# NHK2016mother.net
KiCad netlist of a schematic drawn in EAGLE
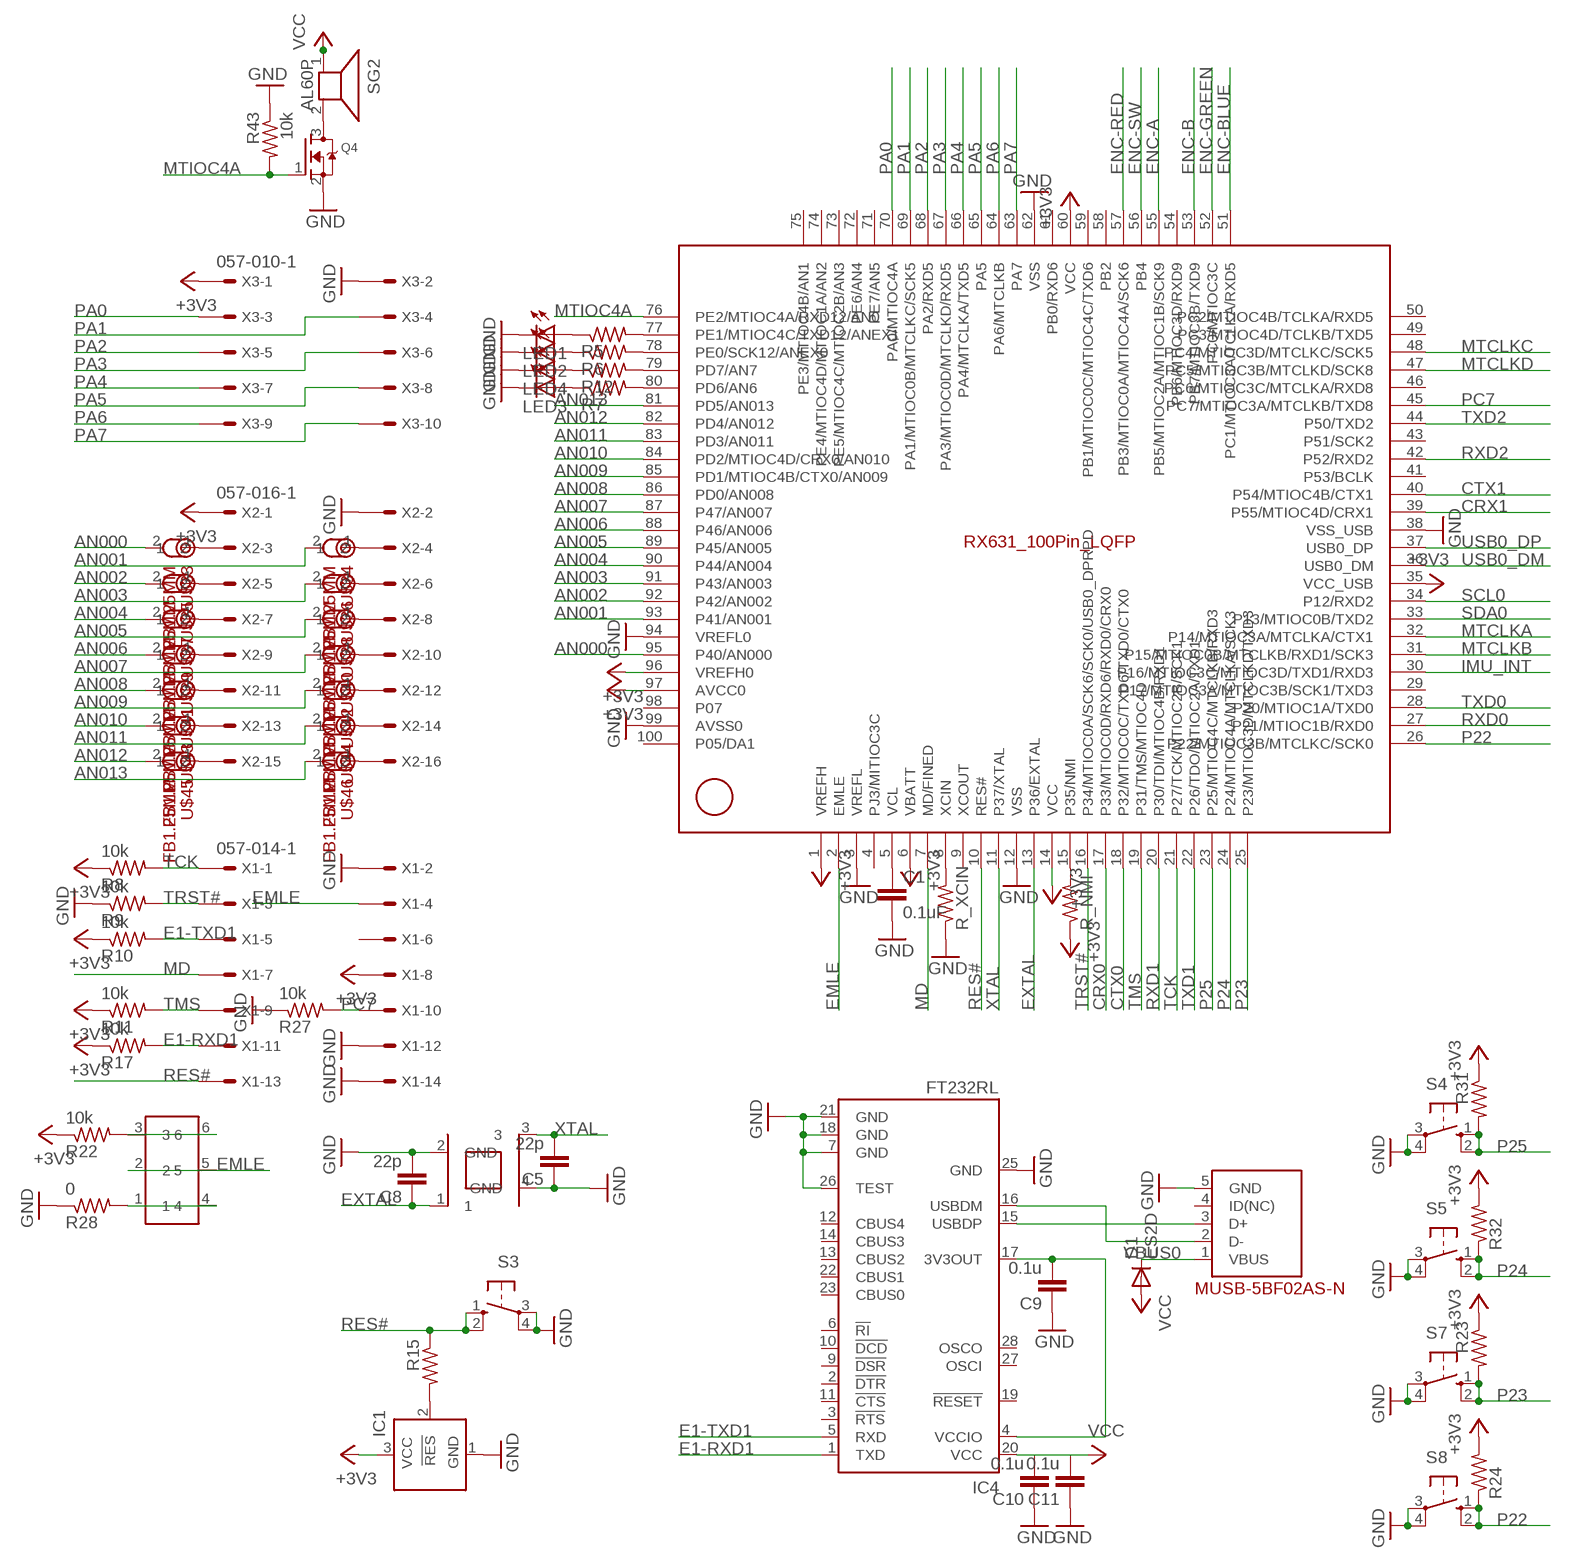
[diagram p0: schematic, sheet 1, part 1 of 2]
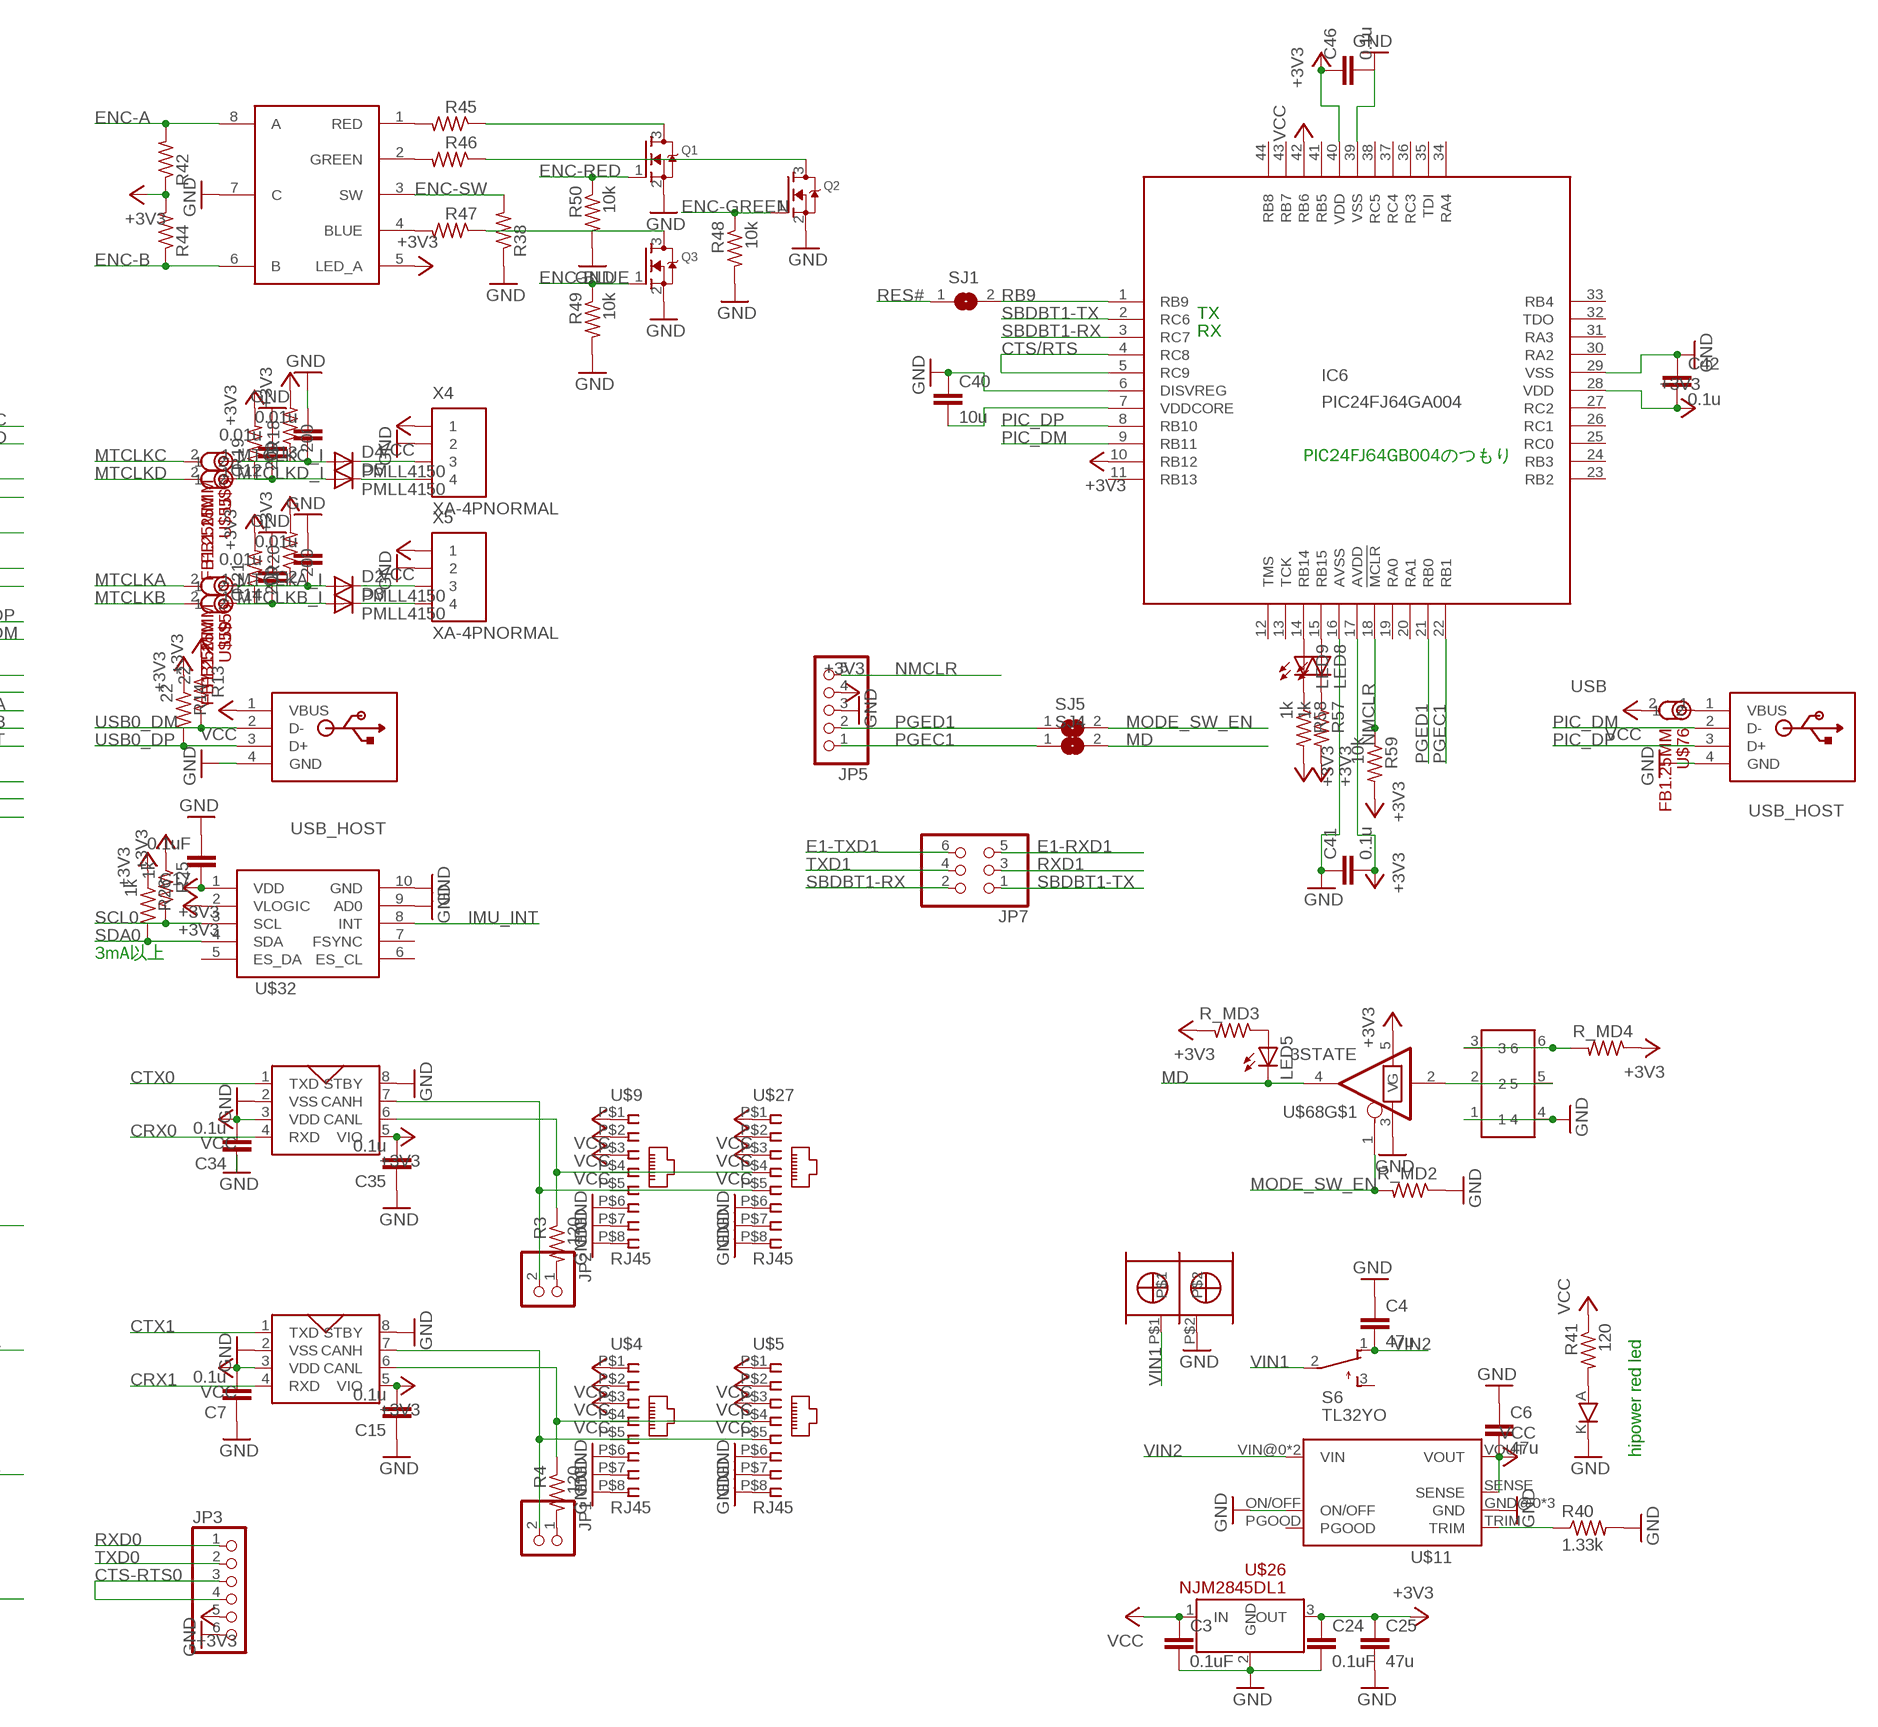
[diagram p1: schematic, sheet 1, part 2 of 2]

(export (version "E")
  (design (tool "Eeschema 10.0.6"))
  (components
    (comp (ref "C1")
      (value "0.1uF")
      (footprint "eagle-import:C0603K")
      (libsource (lib "eagle-import") (part "C-EUC0603K"))
    )
    (comp (ref "C2")
      (value "0.01u")
      (footprint "eagle-import:C0402")
      (libsource (lib "eagle-import") (part "C-EUC0402"))
    )
    (comp (ref "C3")
      (value "0.1uF")
      (footprint "eagle-import:C0603K")
      (libsource (lib "eagle-import") (part "C-EUC0603K"))
    )
    (comp (ref "C4")
      (value "47u")
      (footprint "eagle-import:C3225")
      (libsource (lib "eagle-import") (part "C-EUC3225"))
    )
    (comp (ref "C5")
      (value "22p")
      (footprint "eagle-import:C0603K")
      (libsource (lib "eagle-import") (part "C-EUC0603K"))
    )
    (comp (ref "C6")
      (value "47u")
      (footprint "eagle-import:C3225")
      (libsource (lib "eagle-import") (part "C-EUC3225"))
    )
    (comp (ref "C7")
      (value "0.1u")
      (footprint "eagle-import:C0402")
      (libsource (lib "eagle-import") (part "C-EUC0402"))
    )
    (comp (ref "C8")
      (value "22p")
      (footprint "eagle-import:C0603K")
      (libsource (lib "eagle-import") (part "C-EUC0603K"))
    )
    (comp (ref "C9")
      (value "0.1u")
      (footprint "eagle-import:C0402")
      (libsource (lib "eagle-import") (part "C-EUC0402"))
    )
    (comp (ref "C10")
      (value "0.1u")
      (footprint "eagle-import:C0402")
      (libsource (lib "eagle-import") (part "C-EUC0402"))
    )
    (comp (ref "C11")
      (value "0.1u")
      (footprint "eagle-import:C0402")
      (libsource (lib "eagle-import") (part "C-EUC0402"))
    )
    (comp (ref "C12")
      (value "0.01u")
      (footprint "eagle-import:C0402")
      (libsource (lib "eagle-import") (part "C-EUC0402"))
    )
    (comp (ref "C13")
      (value "0.01u")
      (footprint "eagle-import:C0402")
      (libsource (lib "eagle-import") (part "C-EUC0402"))
    )
    (comp (ref "C14")
      (value "0.01u")
      (footprint "eagle-import:C0402")
      (libsource (lib "eagle-import") (part "C-EUC0402"))
    )
    (comp (ref "C15")
      (value "0.1u")
      (footprint "eagle-import:C0402")
      (libsource (lib "eagle-import") (part "C-EUC0402"))
    )
    (comp (ref "C17")
      (value "0.1uF")
      (footprint "eagle-import:C0603K")
      (libsource (lib "eagle-import") (part "C-EUC0603K"))
    )
    (comp (ref "C24")
      (value "0.1uF")
      (footprint "eagle-import:C0603K")
      (libsource (lib "eagle-import") (part "C-EUC0603K"))
    )
    (comp (ref "C25")
      (value "47u")
      (footprint "eagle-import:C3225")
      (libsource (lib "eagle-import") (part "C-EUC3225"))
    )
    (comp (ref "C34")
      (value "0.1u")
      (footprint "eagle-import:C0402")
      (libsource (lib "eagle-import") (part "C-EUC0402"))
    )
    (comp (ref "C35")
      (value "0.1u")
      (footprint "eagle-import:C0402")
      (libsource (lib "eagle-import") (part "C-EUC0402"))
    )
    (comp (ref "C40")
      (value "10u")
      (footprint "eagle-import:C0603K")
      (libsource (lib "eagle-import") (part "C-EUC0603K"))
    )
    (comp (ref "C41")
      (value "0.1u")
      (footprint "eagle-import:C0603K")
      (libsource (lib "eagle-import") (part "C-EUC0603K"))
    )
    (comp (ref "C42")
      (value "0.1u")
      (footprint "eagle-import:C0603K")
      (libsource (lib "eagle-import") (part "C-EUC0603K"))
    )
    (comp (ref "C46")
      (value "0.1u")
      (footprint "eagle-import:C0603K")
      (libsource (lib "eagle-import") (part "C-EUC0603K"))
    )
    (comp (ref "D1")
      (value "ES2D")
      (footprint "eagle-import:SMB")
      (libsource (lib "eagle-import") (part "ES2D"))
    )
    (comp (ref "D2")
      (value "PMLL4150")
      (footprint "eagle-import:SOD80C")
      (libsource (lib "eagle-import") (part "PMLL4150"))
    )
    (comp (ref "D3")
      (value "PMLL4150")
      (footprint "eagle-import:SOD80C")
      (libsource (lib "eagle-import") (part "PMLL4150"))
    )
    (comp (ref "D4")
      (value "PMLL4150")
      (footprint "eagle-import:SOD80C")
      (libsource (lib "eagle-import") (part "PMLL4150"))
    )
    (comp (ref "D5")
      (value "PMLL4150")
      (footprint "eagle-import:SOD80C")
      (libsource (lib "eagle-import") (part "PMLL4150"))
    )
    (comp (ref "IC1")
      (value "TCM809")
      (footprint "eagle-import:SOT23B-3")
      (fields (field (name "MF") "MICROCHIP") (field (name "MPN") "TCM809MENB713"))
      (libsource (lib "eagle-import") (part "TCM809"))
    )
    (comp (ref "IC4")
      (value "FT232RL")
      (footprint "eagle-import:SSOP28")
      (libsource (lib "eagle-import") (part "FT232RL"))
    )
    (comp (ref "IC6")
      (value "PIC24FJ64GA004")
      (footprint "eagle-import:TQFP44")
      (fields (field (name "MPN") "PIC24FJ64GA004-E/PT"))
      (libsource (lib "eagle-import") (part "PIC24FJ64GA004"))
    )
    (comp (ref "JP1")
      (value "PINHD-1X2")
      (footprint "eagle-import:1X02")
      (libsource (lib "eagle-import") (part "PINHD-1X2"))
    )
    (comp (ref "JP2")
      (value "PINHD-1X2")
      (footprint "eagle-import:1X02")
      (libsource (lib "eagle-import") (part "PINHD-1X2"))
    )
    (comp (ref "JP3")
      (value "PINHD-1X6")
      (footprint "eagle-import:1X06")
      (libsource (lib "eagle-import") (part "PINHD-1X6"))
    )
    (comp (ref "JP5")
      (value "PINHD-1X5")
      (footprint "eagle-import:1X05")
      (libsource (lib "eagle-import") (part "PINHD-1X5"))
    )
    (comp (ref "JP7")
      (value "PINHD-2X3")
      (footprint "eagle-import:2X03")
      (libsource (lib "eagle-import") (part "PINHD-2X3"))
    )
    (comp (ref "LED1")
      (value "LEDSML0805")
      (footprint "eagle-import:SML0805")
      (libsource (lib "eagle-import") (part "LEDSML0805"))
    )
    (comp (ref "LED2")
      (value "LEDSML0805")
      (footprint "eagle-import:SML0805")
      (libsource (lib "eagle-import") (part "LEDSML0805"))
    )
    (comp (ref "LED3")
      (value "LEDSML0805")
      (footprint "eagle-import:SML0805")
      (libsource (lib "eagle-import") (part "LEDSML0805"))
    )
    (comp (ref "LED4")
      (value "LEDSML0805")
      (footprint "eagle-import:SML0805")
      (libsource (lib "eagle-import") (part "LEDSML0805"))
    )
    (comp (ref "LED5")
      (value "LEDSML0805")
      (footprint "eagle-import:SML0805")
      (libsource (lib "eagle-import") (part "LEDSML0805"))
    )
    (comp (ref "LED8")
      (value "LEDSML0805")
      (footprint "eagle-import:SML0805")
      (libsource (lib "eagle-import") (part "LEDSML0805"))
    )
    (comp (ref "LED9")
      (value "LEDSML0805")
      (footprint "eagle-import:SML0805")
      (libsource (lib "eagle-import") (part "LEDSML0805"))
    )
    (comp (ref "Q1")
      (value "MOSFET-NREFLOW")
      (footprint "eagle-import:SOT23")
      (libsource (lib "eagle-import") (part "MOSFET-NREFLOW"))
    )
    (comp (ref "Q2")
      (value "MOSFET-NREFLOW")
      (footprint "eagle-import:SOT23")
      (libsource (lib "eagle-import") (part "MOSFET-NREFLOW"))
    )
    (comp (ref "Q3")
      (value "MOSFET-NREFLOW")
      (footprint "eagle-import:SOT23")
      (libsource (lib "eagle-import") (part "MOSFET-NREFLOW"))
    )
    (comp (ref "Q4")
      (value "MOSFET-NREFLOW")
      (footprint "eagle-import:SOT23")
      (libsource (lib "eagle-import") (part "MOSFET-NREFLOW"))
    )
    (comp (ref "R3")
      (value "120")
      (footprint "eagle-import:MINI_MELF-0102W")
      (libsource (lib "eagle-import") (part "R-US_MELF0102W"))
    )
    (comp (ref "R4")
      (value "120")
      (footprint "eagle-import:MINI_MELF-0102W")
      (libsource (lib "eagle-import") (part "R-US_MELF0102W"))
    )
    (comp (ref "R5")
      (value "R-US_MELF0102W")
      (footprint "eagle-import:MINI_MELF-0102W")
      (libsource (lib "eagle-import") (part "R-US_MELF0102W"))
    )
    (comp (ref "R6")
      (value "R-US_MELF0102W")
      (footprint "eagle-import:MINI_MELF-0102W")
      (libsource (lib "eagle-import") (part "R-US_MELF0102W"))
    )
    (comp (ref "R7")
      (value "R-US_MELF0102W")
      (footprint "eagle-import:MINI_MELF-0102W")
      (libsource (lib "eagle-import") (part "R-US_MELF0102W"))
    )
    (comp (ref "R8")
      (value "10k")
      (footprint "eagle-import:MINI_MELF-0102W")
      (libsource (lib "eagle-import") (part "R-US_MELF0102W"))
    )
    (comp (ref "R9")
      (value "10k")
      (footprint "eagle-import:MINI_MELF-0102W")
      (libsource (lib "eagle-import") (part "R-US_MELF0102W"))
    )
    (comp (ref "R10")
      (value "10k")
      (footprint "eagle-import:MINI_MELF-0102W")
      (libsource (lib "eagle-import") (part "R-US_MELF0102W"))
    )
    (comp (ref "R11")
      (value "10k")
      (footprint "eagle-import:MINI_MELF-0102W")
      (libsource (lib "eagle-import") (part "R-US_MELF0102W"))
    )
    (comp (ref "R12")
      (value "R-US_MELF0102W")
      (footprint "eagle-import:MINI_MELF-0102W")
      (libsource (lib "eagle-import") (part "R-US_MELF0102W"))
    )
    (comp (ref "R13")
      (value "22")
      (footprint "eagle-import:MINI_MELF-0102W")
      (libsource (lib "eagle-import") (part "R-US_MELF0102W"))
    )
    (comp (ref "R14")
      (value "22")
      (footprint "eagle-import:MINI_MELF-0102W")
      (libsource (lib "eagle-import") (part "R-US_MELF0102W"))
    )
    (comp (ref "R15")
      (value "R-US_MELF0102W")
      (footprint "eagle-import:MINI_MELF-0102W")
      (libsource (lib "eagle-import") (part "R-US_MELF0102W"))
    )
    (comp (ref "R17")
      (value "10k")
      (footprint "eagle-import:MINI_MELF-0102W")
      (libsource (lib "eagle-import") (part "R-US_MELF0102W"))
    )
    (comp (ref "R18")
      (value "200")
      (footprint "eagle-import:MINI_MELF-0102W")
      (libsource (lib "eagle-import") (part "R-US_MELF0102W"))
    )
    (comp (ref "R19")
      (value "200")
      (footprint "eagle-import:MINI_MELF-0102W")
      (libsource (lib "eagle-import") (part "R-US_MELF0102W"))
    )
    (comp (ref "R20")
      (value "200")
      (footprint "eagle-import:MINI_MELF-0102W")
      (libsource (lib "eagle-import") (part "R-US_MELF0102W"))
    )
    (comp (ref "R21")
      (value "200")
      (footprint "eagle-import:MINI_MELF-0102W")
      (libsource (lib "eagle-import") (part "R-US_MELF0102W"))
    )
    (comp (ref "R22")
      (value "10k")
      (footprint "eagle-import:MINI_MELF-0102W")
      (libsource (lib "eagle-import") (part "R-US_MELF0102W"))
    )
    (comp (ref "R23")
      (value "R-US_MELF0102W")
      (footprint "eagle-import:MINI_MELF-0102W")
      (libsource (lib "eagle-import") (part "R-US_MELF0102W"))
    )
    (comp (ref "R24")
      (value "R-US_MELF0102W")
      (footprint "eagle-import:MINI_MELF-0102W")
      (libsource (lib "eagle-import") (part "R-US_MELF0102W"))
    )
    (comp (ref "R25")
      (value "1k")
      (footprint "eagle-import:MINI_MELF-0102W")
      (libsource (lib "eagle-import") (part "R-US_MELF0102W"))
    )
    (comp (ref "R26")
      (value "1k")
      (footprint "eagle-import:MINI_MELF-0102W")
      (libsource (lib "eagle-import") (part "R-US_MELF0102W"))
    )
    (comp (ref "R27")
      (value "10k")
      (footprint "eagle-import:MINI_MELF-0102W")
      (libsource (lib "eagle-import") (part "R-US_MELF0102W"))
    )
    (comp (ref "R28")
      (value "0")
      (footprint "eagle-import:MINI_MELF-0102W")
      (libsource (lib "eagle-import") (part "R-US_MELF0102W"))
    )
    (comp (ref "R31")
      (value "R-US_MELF0102W")
      (footprint "eagle-import:MINI_MELF-0102W")
      (libsource (lib "eagle-import") (part "R-US_MELF0102W"))
    )
    (comp (ref "R32")
      (value "R-US_MELF0102W")
      (footprint "eagle-import:MINI_MELF-0102W")
      (libsource (lib "eagle-import") (part "R-US_MELF0102W"))
    )
    (comp (ref "R38")
      (value "R-US_MELF0102W")
      (footprint "eagle-import:MINI_MELF-0102W")
      (libsource (lib "eagle-import") (part "R-US_MELF0102W"))
    )
    (comp (ref "R40")
      (value "1.33k")
      (footprint "eagle-import:MINI_MELF-0102W")
      (libsource (lib "eagle-import") (part "R-US_MELF0102W"))
    )
    (comp (ref "R41")
      (value "120")
      (footprint "eagle-import:MINI_MELF-0102W")
      (libsource (lib "eagle-import") (part "R-US_MELF0102W"))
    )
    (comp (ref "R42")
      (value "R-US_MELF0102W")
      (footprint "eagle-import:MINI_MELF-0102W")
      (libsource (lib "eagle-import") (part "R-US_MELF0102W"))
    )
    (comp (ref "R43")
      (value "10k")
      (footprint "eagle-import:MINI_MELF-0102W")
      (libsource (lib "eagle-import") (part "R-US_MELF0102W"))
    )
    (comp (ref "R44")
      (value "R-US_MELF0102W")
      (footprint "eagle-import:MINI_MELF-0102W")
      (libsource (lib "eagle-import") (part "R-US_MELF0102W"))
    )
    (comp (ref "R45")
      (value "R-US_MELF0102W")
      (footprint "eagle-import:MINI_MELF-0102W")
      (libsource (lib "eagle-import") (part "R-US_MELF0102W"))
    )
    (comp (ref "R46")
      (value "R-US_MELF0102W")
      (footprint "eagle-import:MINI_MELF-0102W")
      (libsource (lib "eagle-import") (part "R-US_MELF0102W"))
    )
    (comp (ref "R47")
      (value "R-US_MELF0102W")
      (footprint "eagle-import:MINI_MELF-0102W")
      (libsource (lib "eagle-import") (part "R-US_MELF0102W"))
    )
    (comp (ref "R48")
      (value "10k")
      (footprint "eagle-import:MINI_MELF-0102W")
      (libsource (lib "eagle-import") (part "R-US_MELF0102W"))
    )
    (comp (ref "R49")
      (value "10k")
      (footprint "eagle-import:MINI_MELF-0102W")
      (libsource (lib "eagle-import") (part "R-US_MELF0102W"))
    )
    (comp (ref "R50")
      (value "10k")
      (footprint "eagle-import:MINI_MELF-0102W")
      (libsource (lib "eagle-import") (part "R-US_MELF0102W"))
    )
    (comp (ref "R57")
      (value "1k")
      (footprint "eagle-import:MINI_MELF-0102W")
      (libsource (lib "eagle-import") (part "R-US_MELF0102W"))
    )
    (comp (ref "R58")
      (value "1k")
      (footprint "eagle-import:MINI_MELF-0102W")
      (libsource (lib "eagle-import") (part "R-US_MELF0102W"))
    )
    (comp (ref "R59")
      (value "10k")
      (footprint "eagle-import:MINI_MELF-0102W")
      (libsource (lib "eagle-import") (part "R-US_MELF0102W"))
    )
    (comp (ref "R_MD2")
      (value "R-US_MELF0102W")
      (footprint "eagle-import:MINI_MELF-0102W")
      (libsource (lib "eagle-import") (part "R-US_MELF0102W"))
    )
    (comp (ref "R_MD3")
      (value "R-US_MELF0102W")
      (footprint "eagle-import:MINI_MELF-0102W")
      (libsource (lib "eagle-import") (part "R-US_MELF0102W"))
    )
    (comp (ref "R_MD4")
      (value "R-US_MELF0102W")
      (footprint "eagle-import:MINI_MELF-0102W")
      (libsource (lib "eagle-import") (part "R-US_MELF0102W"))
    )
    (comp (ref "R_NMI")
      (value "R-US_MELF0102W")
      (footprint "eagle-import:MINI_MELF-0102W")
      (libsource (lib "eagle-import") (part "R-US_MELF0102W"))
    )
    (comp (ref "R_XCIN")
      (value "R-US_MELF0102W")
      (footprint "eagle-import:MINI_MELF-0102W")
      (libsource (lib "eagle-import") (part "R-US_MELF0102W"))
    )
    (comp (ref "S3")
      (value "10-XX")
      (footprint "eagle-import:B3F-10XX")
      (fields (field (name "MPN") "B3F-1000"))
      (libsource (lib "eagle-import") (part "10-XX"))
    )
    (comp (ref "S4")
      (value "10-XX")
      (footprint "eagle-import:B3F-10XX")
      (fields (field (name "MPN") "B3F-1000"))
      (libsource (lib "eagle-import") (part "10-XX"))
    )
    (comp (ref "S5")
      (value "10-XX")
      (footprint "eagle-import:B3F-10XX")
      (fields (field (name "MPN") "B3F-1000"))
      (libsource (lib "eagle-import") (part "10-XX"))
    )
    (comp (ref "S6")
      (value "TL32YO")
      (footprint "eagle-import:TL3XYO")
      (libsource (lib "eagle-import") (part "TL32YO"))
    )
    (comp (ref "S7")
      (value "10-XX")
      (footprint "eagle-import:B3F-10XX")
      (fields (field (name "MPN") "B3F-1000"))
      (libsource (lib "eagle-import") (part "10-XX"))
    )
    (comp (ref "S8")
      (value "10-XX")
      (footprint "eagle-import:B3F-10XX")
      (fields (field (name "MPN") "B3F-1000"))
      (libsource (lib "eagle-import") (part "10-XX"))
    )
    (comp (ref "SG2")
      (value "AL60P")
      (footprint "eagle-import:AL60P")
      (libsource (lib "eagle-import") (part "AL60P"))
    )
    (comp (ref "SJ1") (value "SJ") (footprint "eagle-import:SJ") (libsource (lib "eagle-import") (part "SJ")))
    (comp (ref "SJ4") (value "SJ") (footprint "eagle-import:SJ") (libsource (lib "eagle-import") (part "SJ")))
    (comp (ref "SJ5") (value "SJ") (footprint "eagle-import:SJ") (libsource (lib "eagle-import") (part "SJ")))
    (comp (ref "U$1")
      (value "R5F5631FDDFP")
      (footprint "eagle-import:LQFP100")
      (libsource (lib "eagle-import") (part "R5F5631FDDFP"))
    )
    (comp (ref "U$2")
      (value "MUSB-5BF02AS-N")
      (footprint "eagle-import:MUSB-5BF02AS-N")
      (libsource (lib "eagle-import") (part "MUSB-5BF02AS-N"))
    )
    (comp (ref "U$3")
      (value "MCP2562")
      (footprint "eagle-import:MCP2562")
      (libsource (lib "eagle-import") (part "MCP2562"))
    )
    (comp (ref "U$4")
      (value "RJ45")
      (footprint "eagle-import:RJ45")
      (libsource (lib "eagle-import") (part "RJ45"))
    )
    (comp (ref "U$5")
      (value "RJ45")
      (footprint "eagle-import:RJ45")
      (libsource (lib "eagle-import") (part "RJ45"))
    )
    (comp (ref "U$6")
      (value "FB1.25MM")
      (footprint "eagle-import:2012")
      (libsource (lib "eagle-import") (part "FB1.25MM"))
    )
    (comp (ref "U$7")
      (value "SSSS2")
      (footprint "eagle-import:SSSS2")
      (libsource (lib "eagle-import") (part "SSSS2"))
    )
    (comp (ref "U$8")
      (value "ＦＲ１１０５Ｗ－ＴＲ")
      (footprint "eagle-import:ＦＲ１１０５Ｗ－ＴＲ")
      (libsource (lib "eagle-import") (part "ＦＲ１１０５Ｗ－ＴＲ"))
    )
    (comp (ref "U$9")
      (value "RJ45")
      (footprint "eagle-import:RJ45")
      (libsource (lib "eagle-import") (part "RJ45"))
    )
    (comp (ref "U$10")
      (value "TERMINAL")
      (footprint "eagle-import:TERMINAL")
      (libsource (lib "eagle-import") (part "TERMINAL"))
    )
    (comp (ref "U$11")
      (value "OKL_T6_W12")
      (footprint "eagle-import:OKL_T6_W12")
      (libsource (lib "eagle-import") (part "OKL_T6_W12"))
    )
    (comp (ref "U$17")
      (value "MCP2562")
      (footprint "eagle-import:MCP2562")
      (libsource (lib "eagle-import") (part "MCP2562"))
    )
    (comp (ref "U$26")
      (value "NJM2845DL1")
      (footprint "eagle-import:TO-252-3-L1")
      (libsource (lib "eagle-import") (part "NJM2845DL1"))
    )
    (comp (ref "U$27")
      (value "RJ45")
      (footprint "eagle-import:RJ45")
      (libsource (lib "eagle-import") (part "RJ45"))
    )
    (comp (ref "U$29")
      (value "USB_A")
      (footprint "eagle-import:USB_A")
      (libsource (lib "eagle-import") (part "USB_A"))
    )
    (comp (ref "U$32")
      (value "MPU9150")
      (footprint "eagle-import:MPU9150")
      (libsource (lib "eagle-import") (part "MPU9150"))
    )
    (comp (ref "U$33")
      (value "FB1.25MM")
      (footprint "eagle-import:2012")
      (libsource (lib "eagle-import") (part "FB1.25MM"))
    )
    (comp (ref "U$34")
      (value "FB1.25MM")
      (footprint "eagle-import:2012")
      (libsource (lib "eagle-import") (part "FB1.25MM"))
    )
    (comp (ref "U$35")
      (value "FB1.25MM")
      (footprint "eagle-import:2012")
      (libsource (lib "eagle-import") (part "FB1.25MM"))
    )
    (comp (ref "U$36")
      (value "FB1.25MM")
      (footprint "eagle-import:2012")
      (libsource (lib "eagle-import") (part "FB1.25MM"))
    )
    (comp (ref "U$37")
      (value "FB1.25MM")
      (footprint "eagle-import:2012")
      (libsource (lib "eagle-import") (part "FB1.25MM"))
    )
    (comp (ref "U$38")
      (value "FB1.25MM")
      (footprint "eagle-import:2012")
      (libsource (lib "eagle-import") (part "FB1.25MM"))
    )
    (comp (ref "U$39")
      (value "FB1.25MM")
      (footprint "eagle-import:2012")
      (libsource (lib "eagle-import") (part "FB1.25MM"))
    )
    (comp (ref "U$40")
      (value "FB1.25MM")
      (footprint "eagle-import:2012")
      (libsource (lib "eagle-import") (part "FB1.25MM"))
    )
    (comp (ref "U$41")
      (value "FB1.25MM")
      (footprint "eagle-import:2012")
      (libsource (lib "eagle-import") (part "FB1.25MM"))
    )
    (comp (ref "U$42")
      (value "FB1.25MM")
      (footprint "eagle-import:2012")
      (libsource (lib "eagle-import") (part "FB1.25MM"))
    )
    (comp (ref "U$43")
      (value "FB1.25MM")
      (footprint "eagle-import:2012")
      (libsource (lib "eagle-import") (part "FB1.25MM"))
    )
    (comp (ref "U$44")
      (value "FB1.25MM")
      (footprint "eagle-import:2012")
      (libsource (lib "eagle-import") (part "FB1.25MM"))
    )
    (comp (ref "U$45")
      (value "FB1.25MM")
      (footprint "eagle-import:2012")
      (libsource (lib "eagle-import") (part "FB1.25MM"))
    )
    (comp (ref "U$46")
      (value "FB1.25MM")
      (footprint "eagle-import:2012")
      (libsource (lib "eagle-import") (part "FB1.25MM"))
    )
    (comp (ref "U$55")
      (value "FB1.25MM")
      (footprint "eagle-import:2012")
      (libsource (lib "eagle-import") (part "FB1.25MM"))
    )
    (comp (ref "U$56")
      (value "FB1.25MM")
      (footprint "eagle-import:2012")
      (libsource (lib "eagle-import") (part "FB1.25MM"))
    )
    (comp (ref "U$58")
      (value "EC12PLRGBSDVBF")
      (footprint "eagle-import:EC12PLRGBSDVBF")
      (libsource (lib "eagle-import") (part "EC12PLRGBSDVBF"))
    )
    (comp (ref "U$59")
      (value "FB1.25MM")
      (footprint "eagle-import:2012")
      (libsource (lib "eagle-import") (part "FB1.25MM"))
    )
    (comp (ref "U$61")
      (value "FA238V")
      (footprint "eagle-import:FA238V")
      (libsource (lib "eagle-import") (part "FA238V"))
    )
    (comp (ref "U$68")
      (value "3STATE")
      (footprint "eagle-import:SOT23-5")
      (libsource (lib "eagle-import") (part "3STATE"))
    )
    (comp (ref "U$75")
      (value "USB_A")
      (footprint "eagle-import:USB_A")
      (libsource (lib "eagle-import") (part "USB_A"))
    )
    (comp (ref "U$76")
      (value "FB1.25MM")
      (footprint "eagle-import:2012")
      (libsource (lib "eagle-import") (part "FB1.25MM"))
    )
    (comp (ref "U$82")
      (value "SSSS2")
      (footprint "eagle-import:SSSS2")
      (libsource (lib "eagle-import") (part "SSSS2"))
    )
    (comp (ref "X1")
      (value "057-014-1")
      (footprint "eagle-import:057-014-1")
      (libsource (lib "eagle-import") (part "057-014-1"))
    )
    (comp (ref "X2")
      (value "057-016-1")
      (footprint "eagle-import:057-016-1")
      (libsource (lib "eagle-import") (part "057-016-1"))
    )
    (comp (ref "X3")
      (value "057-010-1")
      (footprint "eagle-import:057-010-1")
      (libsource (lib "eagle-import") (part "057-010-1"))
    )
    (comp (ref "X4")
      (value "XA-4PNORMAL")
      (footprint "eagle-import:XA-4P")
      (libsource (lib "eagle-import") (part "XA-4PNORMAL"))
    )
    (comp (ref "X5")
      (value "XA-4PNORMAL")
      (footprint "eagle-import:XA-4P")
      (libsource (lib "eagle-import") (part "XA-4PNORMAL"))
    )
  )
  (nets
    (net (code "1") (name "+3V3") (class "Default")
      (node (ref "C15") (pin "2") (pinfunction "2_2") (pintype "passive"))
      (node (ref "C17") (pin "1") (pinfunction "1_1") (pintype "passive"))
      (node (ref "C24") (pin "1") (pinfunction "1_1") (pintype "passive"))
      (node (ref "C25") (pin "1") (pinfunction "1_1") (pintype "passive"))
      (node (ref "C35") (pin "2") (pinfunction "2_2") (pintype "passive"))
      (node (ref "C41") (pin "2") (pinfunction "2_2") (pintype "passive"))
      (node (ref "C42") (pin "2") (pinfunction "2_2") (pintype "passive"))
      (node (ref "C46") (pin "1") (pinfunction "1_1") (pintype "passive"))
      (node (ref "IC1") (pin "3") (pinfunction "VCC_3") (pintype "power_in"))
      (node (ref "IC6") (pin "10") (pinfunction "RB12_10") (pintype "bidirectional"))
      (node (ref "IC6") (pin "17") (pinfunction "AVDD_17") (pintype "power_in"))
      (node (ref "IC6") (pin "28") (pinfunction "VDD_28") (pintype "power_in"))
      (node (ref "IC6") (pin "40") (pinfunction "VDD_40") (pintype "power_in"))
      (node (ref "JP3") (pin "5") (pinfunction "5_5") (pintype "passive"))
      (node (ref "JP5") (pin "4") (pinfunction "4_4") (pintype "passive"))
      (node (ref "R10") (pin "1") (pinfunction "1_1") (pintype "passive"))
      (node (ref "R11") (pin "1") (pinfunction "1_1") (pintype "passive"))
      (node (ref "R13") (pin "1") (pinfunction "1_1") (pintype "passive"))
      (node (ref "R14") (pin "1") (pinfunction "1_1") (pintype "passive"))
      (node (ref "R17") (pin "1") (pinfunction "1_1") (pintype "passive"))
      (node (ref "R18") (pin "2") (pinfunction "2_2") (pintype "passive"))
      (node (ref "R19") (pin "2") (pinfunction "2_2") (pintype "passive"))
      (node (ref "R20") (pin "2") (pinfunction "2_2") (pintype "passive"))
      (node (ref "R21") (pin "2") (pinfunction "2_2") (pintype "passive"))
      (node (ref "R22") (pin "1") (pinfunction "1_1") (pintype "passive"))
      (node (ref "R23") (pin "1") (pinfunction "1_1") (pintype "passive"))
      (node (ref "R24") (pin "2") (pinfunction "2_2") (pintype "passive"))
      (node (ref "R25") (pin "1") (pinfunction "1_1") (pintype "passive"))
      (node (ref "R26") (pin "1") (pinfunction "1_1") (pintype "passive"))
      (node (ref "R31") (pin "1") (pinfunction "1_1") (pintype "passive"))
      (node (ref "R32") (pin "2") (pinfunction "2_2") (pintype "passive"))
      (node (ref "R42") (pin "1") (pinfunction "1_1") (pintype "passive"))
      (node (ref "R44") (pin "2") (pinfunction "2_2") (pintype "passive"))
      (node (ref "R57") (pin "2") (pinfunction "2_2") (pintype "passive"))
      (node (ref "R58") (pin "2") (pinfunction "2_2") (pintype "passive"))
      (node (ref "R59") (pin "2") (pinfunction "2_2") (pintype "passive"))
      (node (ref "R8") (pin "1") (pinfunction "1_1") (pintype "passive"))
      (node (ref "R_MD3") (pin "2") (pinfunction "2_2") (pintype "passive"))
      (node (ref "R_MD4") (pin "1") (pinfunction "1_1") (pintype "passive"))
      (node (ref "R_NMI") (pin "1") (pinfunction "1_1") (pintype "passive"))
      (node (ref "U$1") (pin "1") (pinfunction "VREFH_1") (pintype "bidirectional"))
      (node (ref "U$1") (pin "14") (pinfunction "VCC_14") (pintype "bidirectional"))
      (node (ref "U$1") (pin "35") (pinfunction "VCC_USB_35") (pintype "bidirectional"))
      (node (ref "U$1") (pin "6") (pinfunction "VBATT_6") (pintype "bidirectional"))
      (node (ref "U$1") (pin "60") (pinfunction "VCC_60") (pintype "bidirectional"))
      (node (ref "U$1") (pin "96") (pinfunction "VREFH0_96") (pintype "bidirectional"))
      (node (ref "U$1") (pin "97") (pinfunction "AVCC0_97") (pintype "bidirectional"))
      (node (ref "U$17") (pin "5") (pinfunction "VIO_5") (pintype "power_in"))
      (node (ref "U$26") (pin "3") (pinfunction "OUT_3") (pintype "power_in"))
      (node (ref "U$3") (pin "5") (pinfunction "VIO_5") (pintype "power_in"))
      (node (ref "U$32") (pin "1") (pinfunction "VDD_1") (pintype "bidirectional"))
      (node (ref "U$32") (pin "2") (pinfunction "VLOGIC_2") (pintype "bidirectional"))
      (node (ref "U$58") (pin "5") (pinfunction "LED_A_5") (pintype "bidirectional"))
      (node (ref "U$68") (pin "5") (pinfunction "V_5") (pintype "bidirectional"))
      (node (ref "X1") (pin "8") (pinfunction "S_8") (pintype "passive"))
      (node (ref "X2") (pin "1") (pinfunction "S_1") (pintype "passive"))
      (node (ref "X3") (pin "1") (pinfunction "S_1") (pintype "passive"))
    )
    (net (code "2") (name "/AN000") (class "Default")
      (node (ref "U$1") (pin "95") (pinfunction "P40/AN000_95") (pintype "bidirectional"))
      (node (ref "U$33") (pin "2") (pinfunction "2_2") (pintype "passive"))
    )
    (net (code "3") (name "/AN001") (class "Default")
      (node (ref "U$1") (pin "93") (pinfunction "P41/AN001_93") (pintype "bidirectional"))
      (node (ref "U$34") (pin "2") (pinfunction "2_2") (pintype "passive"))
    )
    (net (code "4") (name "/AN002") (class "Default")
      (node (ref "U$1") (pin "92") (pinfunction "P42/AN002_92") (pintype "bidirectional"))
      (node (ref "U$35") (pin "2") (pinfunction "2_2") (pintype "passive"))
    )
    (net (code "5") (name "/AN003") (class "Default")
      (node (ref "U$1") (pin "91") (pinfunction "P43/AN003_91") (pintype "bidirectional"))
      (node (ref "U$36") (pin "2") (pinfunction "2_2") (pintype "passive"))
    )
    (net (code "6") (name "/AN004") (class "Default")
      (node (ref "U$1") (pin "90") (pinfunction "P44/AN004_90") (pintype "bidirectional"))
      (node (ref "U$37") (pin "2") (pinfunction "2_2") (pintype "passive"))
    )
    (net (code "7") (name "/AN005") (class "Default")
      (node (ref "U$1") (pin "89") (pinfunction "P45/AN005_89") (pintype "bidirectional"))
      (node (ref "U$38") (pin "2") (pinfunction "2_2") (pintype "passive"))
    )
    (net (code "8") (name "/AN006") (class "Default")
      (node (ref "U$1") (pin "88") (pinfunction "P46/AN006_88") (pintype "bidirectional"))
      (node (ref "U$39") (pin "2") (pinfunction "2_2") (pintype "passive"))
    )
    (net (code "9") (name "/AN007") (class "Default")
      (node (ref "U$1") (pin "87") (pinfunction "P47/AN007_87") (pintype "bidirectional"))
      (node (ref "U$40") (pin "2") (pinfunction "2_2") (pintype "passive"))
    )
    (net (code "10") (name "/AN008") (class "Default")
      (node (ref "U$1") (pin "86") (pinfunction "PD0/AN008_86") (pintype "bidirectional"))
      (node (ref "U$41") (pin "2") (pinfunction "2_2") (pintype "passive"))
    )
    (net (code "11") (name "/AN009") (class "Default")
      (node (ref "U$1") (pin "85") (pinfunction "PD1/MTIOC4B/CTX0/AN009_85") (pintype "bidirectional"))
      (node (ref "U$42") (pin "2") (pinfunction "2_2") (pintype "passive"))
    )
    (net (code "12") (name "/AN010") (class "Default")
      (node (ref "U$1") (pin "84") (pinfunction "PD2/MTIOC4D/CRX0/AN010_84") (pintype "bidirectional"))
      (node (ref "U$43") (pin "2") (pinfunction "2_2") (pintype "passive"))
    )
    (net (code "13") (name "/AN011") (class "Default")
      (node (ref "U$1") (pin "83") (pinfunction "PD3/AN011_83") (pintype "bidirectional"))
      (node (ref "U$44") (pin "2") (pinfunction "2_2") (pintype "passive"))
    )
    (net (code "14") (name "/AN012") (class "Default")
      (node (ref "U$1") (pin "82") (pinfunction "PD4/AN012_82") (pintype "bidirectional"))
      (node (ref "U$45") (pin "2") (pinfunction "2_2") (pintype "passive"))
    )
    (net (code "15") (name "/AN013") (class "Default")
      (node (ref "U$1") (pin "81") (pinfunction "PD5/AN013_81") (pintype "bidirectional"))
      (node (ref "U$46") (pin "2") (pinfunction "2_2") (pintype "passive"))
    )
    (net (code "16") (name "/CRX0") (class "Default")
      (node (ref "U$1") (pin "17") (pinfunction "P33/MTIOC0D/RXD6/RXD0/CRX0_17") (pintype "bidirectional"))
      (node (ref "U$17") (pin "4") (pinfunction "RXD_4") (pintype "bidirectional"))
    )
    (net (code "17") (name "/CRX1") (class "Default")
      (node (ref "U$1") (pin "39") (pinfunction "P55/MTIOC4D/CRX1_39") (pintype "bidirectional"))
      (node (ref "U$3") (pin "4") (pinfunction "RXD_4") (pintype "bidirectional"))
    )
    (net (code "18") (name "/CTS-RTS0") (class "Default")
      (node (ref "JP3") (pin "3") (pinfunction "3_3") (pintype "passive"))
      (node (ref "JP3") (pin "4") (pinfunction "4_4") (pintype "passive"))
    )
    (net (code "19") (name "/CTS{slash}RTS") (class "Default")
      (node (ref "IC6") (pin "4") (pinfunction "RC8_4") (pintype "bidirectional"))
      (node (ref "IC6") (pin "5") (pinfunction "RC9_5") (pintype "bidirectional"))
    )
    (net (code "20") (name "/CTX0") (class "Default")
      (node (ref "U$1") (pin "18") (pinfunction "P32/MTIOC0C/TXD6/TXD0/CTX0_18") (pintype "bidirectional"))
      (node (ref "U$17") (pin "1") (pinfunction "TXD_1") (pintype "bidirectional"))
    )
    (net (code "21") (name "/CTX1") (class "Default")
      (node (ref "U$1") (pin "40") (pinfunction "P54/MTIOC4B/CTX1_40") (pintype "bidirectional"))
      (node (ref "U$3") (pin "1") (pinfunction "TXD_1") (pintype "bidirectional"))
    )
    (net (code "22") (name "/E1-RXD1") (class "Default")
      (node (ref "IC4") (pin "1") (pinfunction "TXD_1") (pintype "output"))
      (node (ref "JP7") (pin "5") (pinfunction "5_5") (pintype "passive"))
      (node (ref "R17") (pin "2") (pinfunction "2_2") (pintype "passive"))
      (node (ref "X1") (pin "11") (pinfunction "S_11") (pintype "passive"))
    )
    (net (code "23") (name "/E1-TXD1") (class "Default")
      (node (ref "IC4") (pin "5") (pinfunction "RXD_5") (pintype "input"))
      (node (ref "JP7") (pin "6") (pinfunction "6_6") (pintype "passive"))
      (node (ref "R10") (pin "2") (pinfunction "2_2") (pintype "passive"))
      (node (ref "X1") (pin "5") (pinfunction "S_5") (pintype "passive"))
    )
    (net (code "24") (name "/EMLE") (class "Default")
      (node (ref "U$1") (pin "2") (pinfunction "EMLE_2") (pintype "bidirectional"))
      (node (ref "U$7") (pin "2") (pinfunction "2_2") (pintype "bidirectional"))
      (node (ref "U$7") (pin "5") (pinfunction "5_5") (pintype "bidirectional"))
      (node (ref "X1") (pin "4") (pinfunction "S_4") (pintype "passive"))
    )
    (net (code "25") (name "/ENC-A") (class "Default")
      (node (ref "R42") (pin "2") (pinfunction "2_2") (pintype "passive"))
      (node (ref "U$1") (pin "55") (pinfunction "PB5/MTIOC2A/MTIOC1B/SCK9_55") (pintype "bidirectional"))
      (node (ref "U$58") (pin "8") (pinfunction "A_8") (pintype "bidirectional"))
    )
    (net (code "26") (name "/ENC-B") (class "Default")
      (node (ref "R44") (pin "1") (pinfunction "1_1") (pintype "passive"))
      (node (ref "U$1") (pin "53") (pinfunction "PB7/MTIOC3B/TXD9_53") (pintype "bidirectional"))
      (node (ref "U$58") (pin "6") (pinfunction "B_6") (pintype "bidirectional"))
    )
    (net (code "27") (name "/ENC-BLUE") (class "Default")
      (node (ref "Q3") (pin "1") (pinfunction "G_1") (pintype "bidirectional"))
      (node (ref "R49") (pin "1") (pinfunction "1_1") (pintype "passive"))
      (node (ref "U$1") (pin "51") (pinfunction "PC1/MTIOC3A/TCLKA/RXD5_51") (pintype "bidirectional"))
    )
    (net (code "28") (name "/ENC-GREEN") (class "Default")
      (node (ref "Q2") (pin "1") (pinfunction "G_1") (pintype "bidirectional"))
      (node (ref "R48") (pin "1") (pinfunction "1_1") (pintype "passive"))
      (node (ref "U$1") (pin "52") (pinfunction "PC0/MTIOC3C_52") (pintype "bidirectional"))
    )
    (net (code "29") (name "/ENC-RED") (class "Default")
      (node (ref "Q1") (pin "1") (pinfunction "G_1") (pintype "bidirectional"))
      (node (ref "R50") (pin "1") (pinfunction "1_1") (pintype "passive"))
      (node (ref "U$1") (pin "57") (pinfunction "PB3/MTIOC0A/MTIOC4A/SCK6_57") (pintype "bidirectional"))
    )
    (net (code "30") (name "/ENC-SW") (class "Default")
      (node (ref "R38") (pin "2") (pinfunction "2_2") (pintype "passive"))
      (node (ref "U$1") (pin "56") (pinfunction "PB4_56") (pintype "bidirectional"))
      (node (ref "U$58") (pin "3") (pinfunction "SW_3") (pintype "bidirectional"))
    )
    (net (code "31") (name "/EXTAL") (class "Default")
      (node (ref "C8") (pin "1") (pinfunction "1_1") (pintype "passive"))
      (node (ref "U$1") (pin "13") (pinfunction "P36/EXTAL_13") (pintype "bidirectional"))
      (node (ref "U$61") (pin "1") (pinfunction "1_1") (pintype "bidirectional"))
    )
    (net (code "32") (name "/IMU_INT") (class "Default")
      (node (ref "U$1") (pin "30") (pinfunction "P16/MTIOC3C/MTIOC3D/TXD1/RXD3_30") (pintype "bidirectional"))
      (node (ref "U$32") (pin "8") (pinfunction "INT_8") (pintype "bidirectional"))
    )
    (net (code "33") (name "/MD") (class "Default")
      (node (ref "LED5") (pin "C") (pinfunction "C_C") (pintype "passive"))
      (node (ref "SJ4") (pin "2") (pinfunction "2_2") (pintype "passive"))
      (node (ref "U$1") (pin "7") (pinfunction "MD/FINED_7") (pintype "bidirectional"))
      (node (ref "U$68") (pin "4") (pinfunction "O_4") (pintype "tri_state"))
      (node (ref "X1") (pin "7") (pinfunction "S_7") (pintype "passive"))
    )
    (net (code "34") (name "/MODE_SW_EN") (class "Default")
      (node (ref "R_MD2") (pin "2") (pinfunction "2_2") (pintype "passive"))
      (node (ref "SJ5") (pin "2") (pinfunction "2_2") (pintype "passive"))
      (node (ref "U$68") (pin "1") (pinfunction "OE_1") (pintype "input"))
    )
    (net (code "35") (name "/MTCLKA") (class "Default")
      (node (ref "U$1") (pin "32") (pinfunction "P14/MTIOC3A/MTCLKA/CTX1_32") (pintype "bidirectional"))
      (node (ref "U$56") (pin "2") (pinfunction "2_2") (pintype "passive"))
    )
    (net (code "36") (name "/MTCLKA_I") (class "Default")
      (node (ref "C2") (pin "1") (pinfunction "1_1") (pintype "passive"))
      (node (ref "D2") (pin "A") (pinfunction "A_A") (pintype "passive"))
      (node (ref "R20") (pin "1") (pinfunction "1_1") (pintype "passive"))
      (node (ref "U$56") (pin "1") (pinfunction "1_1") (pintype "passive"))
    )
    (net (code "37") (name "/MTCLKB") (class "Default")
      (node (ref "U$1") (pin "31") (pinfunction "P15/MTIOC0B/MTCLKB/RXD1/SCK3_31") (pintype "bidirectional"))
      (node (ref "U$59") (pin "2") (pinfunction "2_2") (pintype "passive"))
    )
    (net (code "38") (name "/MTCLKB_I") (class "Default")
      (node (ref "C14") (pin "1") (pinfunction "1_1") (pintype "passive"))
      (node (ref "D3") (pin "A") (pinfunction "A_A") (pintype "passive"))
      (node (ref "R21") (pin "1") (pinfunction "1_1") (pintype "passive"))
      (node (ref "U$59") (pin "1") (pinfunction "1_1") (pintype "passive"))
    )
    (net (code "39") (name "/MTCLKC") (class "Default")
      (node (ref "U$1") (pin "48") (pinfunction "PC4/MTIOC3D/MTCLKC/SCK5_48") (pintype "bidirectional"))
      (node (ref "U$6") (pin "2") (pinfunction "2_2") (pintype "passive"))
    )
    (net (code "40") (name "/MTCLKC_I") (class "Default")
      (node (ref "C13") (pin "1") (pinfunction "1_1") (pintype "passive"))
      (node (ref "D4") (pin "A") (pinfunction "A_A") (pintype "passive"))
      (node (ref "R18") (pin "1") (pinfunction "1_1") (pintype "passive"))
      (node (ref "U$6") (pin "1") (pinfunction "1_1") (pintype "passive"))
    )
    (net (code "41") (name "/MTCLKD") (class "Default")
      (node (ref "U$1") (pin "47") (pinfunction "PC5/MTIOC3B/MTCLKD/SCK8_47") (pintype "bidirectional"))
      (node (ref "U$55") (pin "2") (pinfunction "2_2") (pintype "passive"))
    )
    (net (code "42") (name "/MTCLKD_I") (class "Default")
      (node (ref "C12") (pin "1") (pinfunction "1_1") (pintype "passive"))
      (node (ref "D5") (pin "A") (pinfunction "A_A") (pintype "passive"))
      (node (ref "R19") (pin "1") (pinfunction "1_1") (pintype "passive"))
      (node (ref "U$55") (pin "1") (pinfunction "1_1") (pintype "passive"))
    )
    (net (code "43") (name "/MTIOC4A") (class "Default")
      (node (ref "Q4") (pin "1") (pinfunction "G_1") (pintype "bidirectional"))
      (node (ref "R43") (pin "2") (pinfunction "2_2") (pintype "passive"))
      (node (ref "U$1") (pin "76") (pinfunction "PE2/MTIOC4A/RXD12/AN0_76") (pintype "bidirectional"))
    )
    (net (code "44") (name "/NMCLR") (class "Default")
      (node (ref "IC6") (pin "18") (pinfunction "~{MCLR}_18") (pintype "bidirectional"))
      (node (ref "JP5") (pin "5") (pinfunction "5_5") (pintype "passive"))
      (node (ref "R59") (pin "1") (pinfunction "1_1") (pintype "passive"))
    )
    (net (code "45") (name "/P22") (class "Default")
      (node (ref "R24") (pin "1") (pinfunction "1_1") (pintype "passive"))
      (node (ref "S8") (pin "1") (pinfunction "S_1") (pintype "passive"))
      (node (ref "S8") (pin "2") (pinfunction "S1_2") (pintype "passive"))
      (node (ref "U$1") (pin "26") (pinfunction "P22/MTIOC3B/MTCLKC/SCK0_26") (pintype "bidirectional"))
    )
    (net (code "46") (name "/P23") (class "Default")
      (node (ref "R23") (pin "2") (pinfunction "2_2") (pintype "passive"))
      (node (ref "S7") (pin "1") (pinfunction "S_1") (pintype "passive"))
      (node (ref "S7") (pin "2") (pinfunction "S1_2") (pintype "passive"))
      (node (ref "U$1") (pin "25") (pinfunction "P23/MTIOC3D/MTCLKD/TXD3_25") (pintype "bidirectional"))
    )
    (net (code "47") (name "/P24") (class "Default")
      (node (ref "R32") (pin "1") (pinfunction "1_1") (pintype "passive"))
      (node (ref "S5") (pin "1") (pinfunction "S_1") (pintype "passive"))
      (node (ref "S5") (pin "2") (pinfunction "S1_2") (pintype "passive"))
      (node (ref "U$1") (pin "24") (pinfunction "P24/MTIOC4A/MTCLKA/SCK3_24") (pintype "bidirectional"))
    )
    (net (code "48") (name "/P25") (class "Default")
      (node (ref "R31") (pin "2") (pinfunction "2_2") (pintype "passive"))
      (node (ref "S4") (pin "1") (pinfunction "S_1") (pintype "passive"))
      (node (ref "S4") (pin "2") (pinfunction "S1_2") (pintype "passive"))
      (node (ref "U$1") (pin "23") (pinfunction "P25/MTIOC4C/MTCLKB/RXD3_23") (pintype "bidirectional"))
    )
    (net (code "49") (name "/PA0") (class "Default")
      (node (ref "U$1") (pin "70") (pinfunction "PA0/MTIOC4A_70") (pintype "bidirectional"))
      (node (ref "X3") (pin "3") (pinfunction "S_3") (pintype "passive"))
    )
    (net (code "50") (name "/PA1") (class "Default")
      (node (ref "U$1") (pin "69") (pinfunction "PA1/MTIOC0B/MTCLKC/SCK5_69") (pintype "bidirectional"))
      (node (ref "X3") (pin "4") (pinfunction "S_4") (pintype "passive"))
    )
    (net (code "51") (name "/PA2") (class "Default")
      (node (ref "U$1") (pin "68") (pinfunction "PA2/RXD5_68") (pintype "bidirectional"))
      (node (ref "X3") (pin "5") (pinfunction "S_5") (pintype "passive"))
    )
    (net (code "52") (name "/PA3") (class "Default")
      (node (ref "U$1") (pin "67") (pinfunction "PA3/MTIOC0D/MTCLKD/RXD5_67") (pintype "bidirectional"))
      (node (ref "X3") (pin "6") (pinfunction "S_6") (pintype "passive"))
    )
    (net (code "53") (name "/PA4") (class "Default")
      (node (ref "U$1") (pin "66") (pinfunction "PA4/MTCLKA/TXD5_66") (pintype "bidirectional"))
      (node (ref "X3") (pin "7") (pinfunction "S_7") (pintype "passive"))
    )
    (net (code "54") (name "/PA5") (class "Default")
      (node (ref "U$1") (pin "65") (pinfunction "PA5_65") (pintype "bidirectional"))
      (node (ref "X3") (pin "8") (pinfunction "S_8") (pintype "passive"))
    )
    (net (code "55") (name "/PA6") (class "Default")
      (node (ref "U$1") (pin "64") (pinfunction "PA6/MTCLKB_64") (pintype "bidirectional"))
      (node (ref "X3") (pin "9") (pinfunction "S_9") (pintype "passive"))
    )
    (net (code "56") (name "/PA7") (class "Default")
      (node (ref "U$1") (pin "63") (pinfunction "PA7_63") (pintype "bidirectional"))
      (node (ref "X3") (pin "10") (pinfunction "S_10") (pintype "passive"))
    )
    (net (code "57") (name "/PC7") (class "Default")
      (node (ref "R27") (pin "2") (pinfunction "2_2") (pintype "passive"))
      (node (ref "U$1") (pin "45") (pinfunction "PC7/MTIOC3A/MTCLKB/TXD8_45") (pintype "bidirectional"))
      (node (ref "X1") (pin "10") (pinfunction "S_10") (pintype "passive"))
    )
    (net (code "58") (name "/PGEC1") (class "Default")
      (node (ref "IC6") (pin "22") (pinfunction "RB1_22") (pintype "bidirectional"))
      (node (ref "JP5") (pin "1") (pinfunction "1_1") (pintype "passive"))
      (node (ref "SJ4") (pin "1") (pinfunction "1_1") (pintype "passive"))
    )
    (net (code "59") (name "/PGED1") (class "Default")
      (node (ref "IC6") (pin "21") (pinfunction "RB0_21") (pintype "bidirectional"))
      (node (ref "JP5") (pin "2") (pinfunction "2_2") (pintype "passive"))
      (node (ref "SJ5") (pin "1") (pinfunction "1_1") (pintype "passive"))
    )
    (net (code "60") (name "/PIC_DM") (class "Default")
      (node (ref "IC6") (pin "9") (pinfunction "RB11_9") (pintype "bidirectional"))
      (node (ref "U$75") (pin "2") (pinfunction "D-_2") (pintype "bidirectional"))
    )
    (net (code "61") (name "/PIC_DP") (class "Default")
      (node (ref "IC6") (pin "8") (pinfunction "RB10_8") (pintype "bidirectional"))
      (node (ref "U$75") (pin "3") (pinfunction "D+_3") (pintype "bidirectional"))
    )
    (net (code "62") (name "/RB9") (class "Default")
      (node (ref "IC6") (pin "1") (pinfunction "RB9_1") (pintype "bidirectional"))
      (node (ref "SJ1") (pin "2") (pinfunction "2_2") (pintype "passive"))
    )
    (net (code "63") (name "/RES#") (class "Default")
      (node (ref "R15") (pin "1") (pinfunction "1_1") (pintype "passive"))
      (node (ref "S3") (pin "1") (pinfunction "S_1") (pintype "passive"))
      (node (ref "S3") (pin "2") (pinfunction "S1_2") (pintype "passive"))
      (node (ref "SJ1") (pin "1") (pinfunction "1_1") (pintype "passive"))
      (node (ref "U$1") (pin "10") (pinfunction "RES#_10") (pintype "bidirectional"))
      (node (ref "X1") (pin "13") (pinfunction "S_13") (pintype "passive"))
    )
    (net (code "64") (name "/RXD0") (class "Default")
      (node (ref "JP3") (pin "1") (pinfunction "1_1") (pintype "passive"))
      (node (ref "U$1") (pin "27") (pinfunction "P21/MTIOC1B/RXD0_27") (pintype "bidirectional"))
    )
    (net (code "65") (name "/RXD1") (class "Default")
      (node (ref "JP7") (pin "3") (pinfunction "3_3") (pintype "passive"))
      (node (ref "U$1") (pin "20") (pinfunction "P30/TDI/MTIOC4B/RXD1_20") (pintype "bidirectional"))
    )
    (net (code "66") (name "/RXD2") (class "Default")
      (node (ref "U$1") (pin "42") (pinfunction "P52/RXD2_42") (pintype "bidirectional"))
    )
    (net (code "67") (name "/SBDBT1-RX") (class "Default")
      (node (ref "IC6") (pin "3") (pinfunction "RC7_3") (pintype "bidirectional"))
      (node (ref "JP7") (pin "2") (pinfunction "2_2") (pintype "passive"))
    )
    (net (code "68") (name "/SBDBT1-TX") (class "Default")
      (node (ref "IC6") (pin "2") (pinfunction "RC6_2") (pintype "bidirectional"))
      (node (ref "JP7") (pin "1") (pinfunction "1_1") (pintype "passive"))
    )
    (net (code "69") (name "/SCL0") (class "Default")
      (node (ref "R25") (pin "2") (pinfunction "2_2") (pintype "passive"))
      (node (ref "U$1") (pin "34") (pinfunction "P12/RXD2_34") (pintype "bidirectional"))
      (node (ref "U$32") (pin "3") (pinfunction "SCL_3") (pintype "bidirectional"))
    )
    (net (code "70") (name "/SDA0") (class "Default")
      (node (ref "R26") (pin "2") (pinfunction "2_2") (pintype "passive"))
      (node (ref "U$1") (pin "33") (pinfunction "P13/MTIOC0B/TXD2_33") (pintype "bidirectional"))
      (node (ref "U$32") (pin "4") (pinfunction "SDA_4") (pintype "bidirectional"))
    )
    (net (code "71") (name "/TCK") (class "Default")
      (node (ref "R8") (pin "2") (pinfunction "2_2") (pintype "passive"))
      (node (ref "U$1") (pin "21") (pinfunction "P27/TCK/MTIOC2B/SCK1_21") (pintype "bidirectional"))
      (node (ref "X1") (pin "1") (pinfunction "S_1") (pintype "passive"))
    )
    (net (code "72") (name "/TMS") (class "Default")
      (node (ref "R11") (pin "2") (pinfunction "2_2") (pintype "passive"))
      (node (ref "U$1") (pin "19") (pinfunction "P31/TMS/MTIOC4D_19") (pintype "bidirectional"))
      (node (ref "X1") (pin "9") (pinfunction "S_9") (pintype "passive"))
    )
    (net (code "73") (name "/TRST#") (class "Default")
      (node (ref "R9") (pin "2") (pinfunction "2_2") (pintype "passive"))
      (node (ref "U$1") (pin "16") (pinfunction "P34/MTIOC0A/SCK6/SCK0/USB0_DPRPD_16") (pintype "bidirectional"))
      (node (ref "X1") (pin "3") (pinfunction "S_3") (pintype "passive"))
    )
    (net (code "74") (name "/TXD0") (class "Default")
      (node (ref "JP3") (pin "2") (pinfunction "2_2") (pintype "passive"))
      (node (ref "U$1") (pin "28") (pinfunction "P20/MTIOC1A/TXD0_28") (pintype "bidirectional"))
    )
    (net (code "75") (name "/TXD1") (class "Default")
      (node (ref "JP7") (pin "4") (pinfunction "4_4") (pintype "passive"))
      (node (ref "U$1") (pin "22") (pinfunction "P26/TDO/MTIOC2A/TXD1_22") (pintype "bidirectional"))
    )
    (net (code "76") (name "/TXD2") (class "Default")
      (node (ref "U$1") (pin "44") (pinfunction "P50/TXD2_44") (pintype "bidirectional"))
    )
    (net (code "77") (name "/USB0_DM") (class "Default")
      (node (ref "R13") (pin "2") (pinfunction "2_2") (pintype "passive"))
      (node (ref "U$1") (pin "36") (pinfunction "USB0_DM_36") (pintype "bidirectional"))
      (node (ref "U$29") (pin "2") (pinfunction "D-_2") (pintype "bidirectional"))
    )
    (net (code "78") (name "/USB0_DP") (class "Default")
      (node (ref "R14") (pin "2") (pinfunction "2_2") (pintype "passive"))
      (node (ref "U$1") (pin "37") (pinfunction "USB0_DP_37") (pintype "bidirectional"))
      (node (ref "U$29") (pin "3") (pinfunction "D+_3") (pintype "bidirectional"))
    )
    (net (code "79") (name "/VBUS0") (class "Default")
      (node (ref "D1") (pin "C") (pinfunction "C_C") (pintype "passive"))
      (node (ref "U$2") (pin "1") (pinfunction "VBUS_1") (pintype "bidirectional"))
    )
    (net (code "80") (name "/VIN1") (class "Default")
      (node (ref "S6") (pin "2") (pinfunction "P_2") (pintype "passive"))
      (node (ref "U$10") (pin "P$1") (pinfunction "P$1_P$1") (pintype "bidirectional"))
    )
    (net (code "81") (name "/VIN2") (class "Default")
      (node (ref "C4") (pin "2") (pinfunction "2_2") (pintype "passive"))
      (node (ref "S6") (pin "1") (pinfunction "O_1") (pintype "passive"))
      (node (ref "U$11") (pin "VIN@0") (pinfunction "VIN_VIN@0") (pintype "bidirectional"))
      (node (ref "U$11") (pin "VIN@1") (pinfunction "VIN_VIN@1") (pintype "bidirectional"))
    )
    (net (code "82") (name "/XTAL") (class "Default")
      (node (ref "C5") (pin "2") (pinfunction "2_2") (pintype "passive"))
      (node (ref "U$1") (pin "11") (pinfunction "P37/XTAL_11") (pintype "bidirectional"))
      (node (ref "U$61") (pin "3") (pinfunction "3_3") (pintype "bidirectional"))
    )
    (net (code "83") (name "GND") (class "Default")
      (node (ref "C1") (pin "2") (pinfunction "2_2") (pintype "passive"))
      (node (ref "C10") (pin "1") (pinfunction "1_1") (pintype "passive"))
      (node (ref "C11") (pin "1") (pinfunction "1_1") (pintype "passive"))
      (node (ref "C12") (pin "2") (pinfunction "2_2") (pintype "passive"))
      (node (ref "C13") (pin "2") (pinfunction "2_2") (pintype "passive"))
      (node (ref "C14") (pin "2") (pinfunction "2_2") (pintype "passive"))
      (node (ref "C15") (pin "1") (pinfunction "1_1") (pintype "passive"))
      (node (ref "C17") (pin "2") (pinfunction "2_2") (pintype "passive"))
      (node (ref "C2") (pin "2") (pinfunction "2_2") (pintype "passive"))
      (node (ref "C24") (pin "2") (pinfunction "2_2") (pintype "passive"))
      (node (ref "C25") (pin "2") (pinfunction "2_2") (pintype "passive"))
      (node (ref "C3") (pin "2") (pinfunction "2_2") (pintype "passive"))
      (node (ref "C34") (pin "1") (pinfunction "1_1") (pintype "passive"))
      (node (ref "C35") (pin "1") (pinfunction "1_1") (pintype "passive"))
      (node (ref "C4") (pin "1") (pinfunction "1_1") (pintype "passive"))
      (node (ref "C40") (pin "1") (pinfunction "1_1") (pintype "passive"))
      (node (ref "C41") (pin "1") (pinfunction "1_1") (pintype "passive"))
      (node (ref "C42") (pin "1") (pinfunction "1_1") (pintype "passive"))
      (node (ref "C46") (pin "2") (pinfunction "2_2") (pintype "passive"))
      (node (ref "C5") (pin "1") (pinfunction "1_1") (pintype "passive"))
      (node (ref "C6") (pin "1") (pinfunction "1_1") (pintype "passive"))
      (node (ref "C7") (pin "1") (pinfunction "1_1") (pintype "passive"))
      (node (ref "C8") (pin "2") (pinfunction "2_2") (pintype "passive"))
      (node (ref "C9") (pin "1") (pinfunction "1_1") (pintype "passive"))
      (node (ref "IC1") (pin "1") (pinfunction "GND_1") (pintype "power_in"))
      (node (ref "IC4") (pin "18") (pinfunction "GND_18") (pintype "power_in"))
      (node (ref "IC4") (pin "21") (pinfunction "GND_21") (pintype "power_in"))
      (node (ref "IC4") (pin "25") (pinfunction "GND_25") (pintype "power_in"))
      (node (ref "IC4") (pin "26") (pinfunction "TEST_26") (pintype "input"))
      (node (ref "IC4") (pin "7") (pinfunction "GND_7") (pintype "power_in"))
      (node (ref "IC6") (pin "16") (pinfunction "AVSS_16") (pintype "power_in"))
      (node (ref "IC6") (pin "29") (pinfunction "VSS_29") (pintype "power_in"))
      (node (ref "IC6") (pin "39") (pinfunction "VSS_39") (pintype "power_in"))
      (node (ref "IC6") (pin "6") (pinfunction "DISVREG_6") (pintype "passive"))
      (node (ref "JP3") (pin "6") (pinfunction "6_6") (pintype "passive"))
      (node (ref "JP5") (pin "3") (pinfunction "3_3") (pintype "passive"))
      (node (ref "LED1") (pin "C") (pinfunction "C_C") (pintype "passive"))
      (node (ref "LED2") (pin "C") (pinfunction "C_C") (pintype "passive"))
      (node (ref "LED3") (pin "C") (pinfunction "C_C") (pintype "passive"))
      (node (ref "LED4") (pin "C") (pinfunction "C_C") (pintype "passive"))
      (node (ref "Q1") (pin "2") (pinfunction "S_2") (pintype "bidirectional"))
      (node (ref "Q2") (pin "2") (pinfunction "S_2") (pintype "bidirectional"))
      (node (ref "Q3") (pin "2") (pinfunction "S_2") (pintype "bidirectional"))
      (node (ref "Q4") (pin "2") (pinfunction "S_2") (pintype "bidirectional"))
      (node (ref "R27") (pin "1") (pinfunction "1_1") (pintype "passive"))
      (node (ref "R28") (pin "1") (pinfunction "1_1") (pintype "passive"))
      (node (ref "R38") (pin "1") (pinfunction "1_1") (pintype "passive"))
      (node (ref "R40") (pin "2") (pinfunction "2_2") (pintype "passive"))
      (node (ref "R43") (pin "1") (pinfunction "1_1") (pintype "passive"))
      (node (ref "R48") (pin "2") (pinfunction "2_2") (pintype "passive"))
      (node (ref "R49") (pin "2") (pinfunction "2_2") (pintype "passive"))
      (node (ref "R50") (pin "2") (pinfunction "2_2") (pintype "passive"))
      (node (ref "R9") (pin "1") (pinfunction "1_1") (pintype "passive"))
      (node (ref "R_MD2") (pin "1") (pinfunction "1_1") (pintype "passive"))
      (node (ref "R_XCIN") (pin "1") (pinfunction "1_1") (pintype "passive"))
      (node (ref "S3") (pin "3") (pinfunction "P_3") (pintype "passive"))
      (node (ref "S3") (pin "4") (pinfunction "P1_4") (pintype "passive"))
      (node (ref "S4") (pin "3") (pinfunction "P_3") (pintype "passive"))
      (node (ref "S4") (pin "4") (pinfunction "P1_4") (pintype "passive"))
      (node (ref "S5") (pin "3") (pinfunction "P_3") (pintype "passive"))
      (node (ref "S5") (pin "4") (pinfunction "P1_4") (pintype "passive"))
      (node (ref "S7") (pin "3") (pinfunction "P_3") (pintype "passive"))
      (node (ref "S7") (pin "4") (pinfunction "P1_4") (pintype "passive"))
      (node (ref "S8") (pin "3") (pinfunction "P_3") (pintype "passive"))
      (node (ref "S8") (pin "4") (pinfunction "P1_4") (pintype "passive"))
      (node (ref "U$1") (pin "12") (pinfunction "VSS_12") (pintype "bidirectional"))
      (node (ref "U$1") (pin "3") (pinfunction "VREFL_3") (pintype "bidirectional"))
      (node (ref "U$1") (pin "38") (pinfunction "VSS_USB_38") (pintype "bidirectional"))
      (node (ref "U$1") (pin "62") (pinfunction "VSS_62") (pintype "bidirectional"))
      (node (ref "U$1") (pin "94") (pinfunction "VREFL0_94") (pintype "bidirectional"))
      (node (ref "U$1") (pin "99") (pinfunction "AVSS0_99") (pintype "bidirectional"))
      (node (ref "U$10") (pin "P$2") (pinfunction "P$2_P$2") (pintype "bidirectional"))
      (node (ref "U$11") (pin "GND@0") (pinfunction "GND_GND@0") (pintype "bidirectional"))
      (node (ref "U$11") (pin "GND@1") (pinfunction "GND_GND@1") (pintype "bidirectional"))
      (node (ref "U$11") (pin "GND@2") (pinfunction "GND_GND@2") (pintype "bidirectional"))
      (node (ref "U$11") (pin "ON/OFF") (pinfunction "ON/OFF_ON/OFF") (pintype "bidirectional"))
      (node (ref "U$17") (pin "2") (pinfunction "VSS_2") (pintype "power_in"))
      (node (ref "U$17") (pin "8") (pinfunction "STBY_8") (pintype "bidirectional"))
      (node (ref "U$2") (pin "5") (pinfunction "GND_5") (pintype "bidirectional"))
      (node (ref "U$26") (pin "2") (pinfunction "GND_2") (pintype "power_in"))
      (node (ref "U$27") (pin "P$6") (pinfunction "6_P$6") (pintype "passive"))
      (node (ref "U$27") (pin "P$7") (pinfunction "7_P$7") (pintype "passive"))
      (node (ref "U$27") (pin "P$8") (pinfunction "8_P$8") (pintype "passive"))
      (node (ref "U$29") (pin "4") (pinfunction "GND_4") (pintype "bidirectional"))
      (node (ref "U$3") (pin "2") (pinfunction "VSS_2") (pintype "power_in"))
      (node (ref "U$3") (pin "8") (pinfunction "STBY_8") (pintype "bidirectional"))
      (node (ref "U$32") (pin "10") (pinfunction "GND_10") (pintype "bidirectional"))
      (node (ref "U$32") (pin "9") (pinfunction "AD0_9") (pintype "bidirectional"))
      (node (ref "U$4") (pin "P$6") (pinfunction "6_P$6") (pintype "passive"))
      (node (ref "U$4") (pin "P$7") (pinfunction "7_P$7") (pintype "passive"))
      (node (ref "U$4") (pin "P$8") (pinfunction "8_P$8") (pintype "passive"))
      (node (ref "U$5") (pin "P$6") (pinfunction "6_P$6") (pintype "passive"))
      (node (ref "U$5") (pin "P$7") (pinfunction "7_P$7") (pintype "passive"))
      (node (ref "U$5") (pin "P$8") (pinfunction "8_P$8") (pintype "passive"))
      (node (ref "U$58") (pin "7") (pinfunction "C_7") (pintype "bidirectional"))
      (node (ref "U$61") (pin "2") (pinfunction "GND_2") (pintype "power_in"))
      (node (ref "U$61") (pin "4") (pinfunction "GND_4") (pintype "power_in"))
      (node (ref "U$68") (pin "3") (pinfunction "G_3") (pintype "bidirectional"))
      (node (ref "U$75") (pin "4") (pinfunction "GND_4") (pintype "bidirectional"))
      (node (ref "U$8") (pin "K") (pinfunction "K_K") (pintype "bidirectional"))
      (node (ref "U$82") (pin "1") (pinfunction "1_1") (pintype "bidirectional"))
      (node (ref "U$82") (pin "4") (pinfunction "4_4") (pintype "bidirectional"))
      (node (ref "U$9") (pin "P$6") (pinfunction "6_P$6") (pintype "passive"))
      (node (ref "U$9") (pin "P$7") (pinfunction "7_P$7") (pintype "passive"))
      (node (ref "U$9") (pin "P$8") (pinfunction "8_P$8") (pintype "passive"))
      (node (ref "X1") (pin "12") (pinfunction "S_12") (pintype "passive"))
      (node (ref "X1") (pin "14") (pinfunction "S_14") (pintype "passive"))
      (node (ref "X1") (pin "2") (pinfunction "S_2") (pintype "passive"))
      (node (ref "X2") (pin "2") (pinfunction "S_2") (pintype "passive"))
      (node (ref "X3") (pin "2") (pinfunction "S_2") (pintype "passive"))
      (node (ref "X4") (pin "2") (pinfunction "2_2") (pintype "bidirectional"))
      (node (ref "X5") (pin "2") (pinfunction "2_2") (pintype "bidirectional"))
    )
    (net (code "84") (name "Net-(D2-PadC)") (class "Default")
      (node (ref "D2") (pin "C") (pinfunction "C_C") (pintype "passive"))
      (node (ref "X5") (pin "3") (pinfunction "3_3") (pintype "bidirectional"))
    )
    (net (code "85") (name "Net-(D3-PadC)") (class "Default")
      (node (ref "D3") (pin "C") (pinfunction "C_C") (pintype "passive"))
      (node (ref "X5") (pin "4") (pinfunction "4_4") (pintype "bidirectional"))
    )
    (net (code "86") (name "Net-(D4-PadC)") (class "Default")
      (node (ref "D4") (pin "C") (pinfunction "C_C") (pintype "passive"))
      (node (ref "X4") (pin "3") (pinfunction "3_3") (pintype "bidirectional"))
    )
    (net (code "87") (name "Net-(D5-PadC)") (class "Default")
      (node (ref "D5") (pin "C") (pinfunction "C_C") (pintype "passive"))
      (node (ref "X4") (pin "4") (pinfunction "4_4") (pintype "bidirectional"))
    )
    (net (code "88") (name "Net-(IC1-~{RES})") (class "Default")
      (node (ref "IC1") (pin "2") (pinfunction "~{RES}_2") (pintype "output"))
      (node (ref "R15") (pin "2") (pinfunction "2_2") (pintype "passive"))
    )
    (net (code "89") (name "Net-(IC4-3V3OUT)") (class "Default")
      (node (ref "C9") (pin "2") (pinfunction "2_2") (pintype "passive"))
      (node (ref "IC4") (pin "17") (pinfunction "3V3OUT_17") (pintype "output"))
      (node (ref "IC4") (pin "4") (pinfunction "VCCIO_4") (pintype "power_in"))
    )
    (net (code "90") (name "Net-(IC4-USBDM)") (class "Default")
      (node (ref "IC4") (pin "16") (pinfunction "USBDM_16") (pintype "bidirectional"))
      (node (ref "U$2") (pin "2") (pinfunction "D-_2") (pintype "bidirectional"))
    )
    (net (code "91") (name "Net-(IC4-USBDP)") (class "Default")
      (node (ref "IC4") (pin "15") (pinfunction "USBDP_15") (pintype "bidirectional"))
      (node (ref "U$2") (pin "3") (pinfunction "D+_3") (pintype "bidirectional"))
    )
    (net (code "92") (name "Net-(IC6-RB14)") (class "Default")
      (node (ref "IC6") (pin "14") (pinfunction "RB14_14") (pintype "bidirectional"))
      (node (ref "LED9") (pin "A") (pinfunction "A_A") (pintype "passive"))
    )
    (net (code "93") (name "Net-(IC6-RB15)") (class "Default")
      (node (ref "IC6") (pin "15") (pinfunction "RB15_15") (pintype "bidirectional"))
      (node (ref "LED8") (pin "A") (pinfunction "A_A") (pintype "passive"))
    )
    (net (code "94") (name "Net-(IC6-VDDCORE)") (class "Default")
      (node (ref "C40") (pin "2") (pinfunction "2_2") (pintype "passive"))
      (node (ref "IC6") (pin "7") (pinfunction "VDDCORE_7") (pintype "power_in"))
    )
    (net (code "95") (name "Net-(JP1-Pad1)") (class "Default")
      (node (ref "JP1") (pin "1") (pinfunction "1_1") (pintype "passive"))
      (node (ref "R4") (pin "2") (pinfunction "2_2") (pintype "passive"))
    )
    (net (code "96") (name "Net-(JP2-Pad1)") (class "Default")
      (node (ref "JP2") (pin "1") (pinfunction "1_1") (pintype "passive"))
      (node (ref "R3") (pin "2") (pinfunction "2_2") (pintype "passive"))
    )
    (net (code "97") (name "Net-(LED1-PadA)") (class "Default")
      (node (ref "LED1") (pin "A") (pinfunction "A_A") (pintype "passive"))
      (node (ref "R5") (pin "1") (pinfunction "1_1") (pintype "passive"))
    )
    (net (code "98") (name "Net-(LED2-PadA)") (class "Default")
      (node (ref "LED2") (pin "A") (pinfunction "A_A") (pintype "passive"))
      (node (ref "R6") (pin "1") (pinfunction "1_1") (pintype "passive"))
    )
    (net (code "99") (name "Net-(LED3-PadA)") (class "Default")
      (node (ref "LED3") (pin "A") (pinfunction "A_A") (pintype "passive"))
      (node (ref "R7") (pin "1") (pinfunction "1_1") (pintype "passive"))
    )
    (net (code "100") (name "Net-(LED4-PadA)") (class "Default")
      (node (ref "LED4") (pin "A") (pinfunction "A_A") (pintype "passive"))
      (node (ref "R12") (pin "1") (pinfunction "1_1") (pintype "passive"))
    )
    (net (code "101") (name "Net-(LED5-PadA)") (class "Default")
      (node (ref "LED5") (pin "A") (pinfunction "A_A") (pintype "passive"))
      (node (ref "R_MD3") (pin "1") (pinfunction "1_1") (pintype "passive"))
    )
    (net (code "102") (name "Net-(LED8-PadC)") (class "Default")
      (node (ref "LED8") (pin "C") (pinfunction "C_C") (pintype "passive"))
      (node (ref "R57") (pin "1") (pinfunction "1_1") (pintype "passive"))
    )
    (net (code "103") (name "Net-(LED9-PadC)") (class "Default")
      (node (ref "LED9") (pin "C") (pinfunction "C_C") (pintype "passive"))
      (node (ref "R58") (pin "1") (pinfunction "1_1") (pintype "passive"))
    )
    (net (code "104") (name "Net-(Q1-D)") (class "Default")
      (node (ref "Q1") (pin "3") (pinfunction "D_3") (pintype "bidirectional"))
      (node (ref "R45") (pin "1") (pinfunction "1_1") (pintype "passive"))
    )
    (net (code "105") (name "Net-(Q2-D)") (class "Default")
      (node (ref "Q2") (pin "3") (pinfunction "D_3") (pintype "bidirectional"))
      (node (ref "R46") (pin "1") (pinfunction "1_1") (pintype "passive"))
    )
    (net (code "106") (name "Net-(Q3-D)") (class "Default")
      (node (ref "Q3") (pin "3") (pinfunction "D_3") (pintype "bidirectional"))
      (node (ref "R47") (pin "1") (pinfunction "1_1") (pintype "passive"))
    )
    (net (code "107") (name "Net-(Q4-D)") (class "Default")
      (node (ref "Q4") (pin "3") (pinfunction "D_3") (pintype "bidirectional"))
      (node (ref "SG2") (pin "2") (pinfunction "2_2") (pintype "passive"))
    )
    (net (code "108") (name "Net-(R22-Pad2)") (class "Default")
      (node (ref "R22") (pin "2") (pinfunction "2_2") (pintype "passive"))
      (node (ref "U$7") (pin "3") (pinfunction "3_3") (pintype "bidirectional"))
      (node (ref "U$7") (pin "6") (pinfunction "6_6") (pintype "bidirectional"))
    )
    (net (code "109") (name "Net-(R28-Pad2)") (class "Default")
      (node (ref "R28") (pin "2") (pinfunction "2_2") (pintype "passive"))
      (node (ref "U$7") (pin "1") (pinfunction "1_1") (pintype "bidirectional"))
      (node (ref "U$7") (pin "4") (pinfunction "4_4") (pintype "bidirectional"))
    )
    (net (code "110") (name "Net-(R40-Pad1)") (class "Default")
      (node (ref "R40") (pin "1") (pinfunction "1_1") (pintype "passive"))
      (node (ref "U$11") (pin "TRIM") (pinfunction "TRIM_TRIM") (pintype "bidirectional"))
    )
    (net (code "111") (name "Net-(R41-Pad2)") (class "Default")
      (node (ref "R41") (pin "2") (pinfunction "2_2") (pintype "passive"))
      (node (ref "U$8") (pin "A") (pinfunction "A_A") (pintype "bidirectional"))
    )
    (net (code "112") (name "Net-(R_MD4-Pad2)") (class "Default")
      (node (ref "R_MD4") (pin "2") (pinfunction "2_2") (pintype "passive"))
      (node (ref "U$82") (pin "3") (pinfunction "3_3") (pintype "bidirectional"))
      (node (ref "U$82") (pin "6") (pinfunction "6_6") (pintype "bidirectional"))
    )
    (net (code "113") (name "Net-(U$1-P35{slash}NMI)") (class "Default")
      (node (ref "R_NMI") (pin "2") (pinfunction "2_2") (pintype "passive"))
      (node (ref "U$1") (pin "15") (pinfunction "P35/NMI_15") (pintype "bidirectional"))
    )
    (net (code "114") (name "Net-(U$1-PD6{slash}AN6)") (class "Default")
      (node (ref "R7") (pin "2") (pinfunction "2_2") (pintype "passive"))
      (node (ref "U$1") (pin "80") (pinfunction "PD6/AN6_80") (pintype "bidirectional"))
    )
    (net (code "115") (name "Net-(U$1-PD7{slash}AN7)") (class "Default")
      (node (ref "R12") (pin "2") (pinfunction "2_2") (pintype "passive"))
      (node (ref "U$1") (pin "79") (pinfunction "PD7/AN7_79") (pintype "bidirectional"))
    )
    (net (code "116") (name "Net-(U$1-PE0{slash}SCK12{slash}ANEX0)") (class "Default")
      (node (ref "R6") (pin "2") (pinfunction "2_2") (pintype "passive"))
      (node (ref "U$1") (pin "78") (pinfunction "PE0/SCK12/ANEX0_78") (pintype "bidirectional"))
    )
    (net (code "117") (name "Net-(U$1-PE1{slash}MTIOC4C{slash}TXD12{slash}ANEX1)") (class "Default")
      (node (ref "R5") (pin "2") (pinfunction "2_2") (pintype "passive"))
      (node (ref "U$1") (pin "77") (pinfunction "PE1/MTIOC4C/TXD12/ANEX1_77") (pintype "bidirectional"))
    )
    (net (code "118") (name "Net-(U$1-VCL)") (class "Default")
      (node (ref "C1") (pin "1") (pinfunction "1_1") (pintype "passive"))
      (node (ref "U$1") (pin "5") (pinfunction "VCL_5") (pintype "bidirectional"))
    )
    (net (code "119") (name "Net-(U$1-XCIN)") (class "Default")
      (node (ref "R_XCIN") (pin "2") (pinfunction "2_2") (pintype "passive"))
      (node (ref "U$1") (pin "8") (pinfunction "XCIN_8") (pintype "bidirectional"))
    )
    (net (code "120") (name "Net-(U$3-CANH)") (class "Default")
      (node (ref "JP1") (pin "2") (pinfunction "2_2") (pintype "passive"))
      (node (ref "U$3") (pin "7") (pinfunction "CANH_7") (pintype "bidirectional"))
      (node (ref "U$4") (pin "P$5") (pinfunction "5_P$5") (pintype "passive"))
      (node (ref "U$5") (pin "P$5") (pinfunction "5_P$5") (pintype "passive"))
    )
    (net (code "121") (name "Net-(U$3-CANL)") (class "Default")
      (node (ref "R4") (pin "1") (pinfunction "1_1") (pintype "passive"))
      (node (ref "U$3") (pin "6") (pinfunction "CANL_6") (pintype "bidirectional"))
      (node (ref "U$4") (pin "P$4") (pinfunction "4_P$4") (pintype "passive"))
      (node (ref "U$5") (pin "P$4") (pinfunction "4_P$4") (pintype "passive"))
    )
    (net (code "122") (name "Net-(U$17-CANH)") (class "Default")
      (node (ref "JP2") (pin "2") (pinfunction "2_2") (pintype "passive"))
      (node (ref "U$17") (pin "7") (pinfunction "CANH_7") (pintype "bidirectional"))
      (node (ref "U$27") (pin "P$5") (pinfunction "5_P$5") (pintype "passive"))
      (node (ref "U$9") (pin "P$5") (pinfunction "5_P$5") (pintype "passive"))
    )
    (net (code "123") (name "Net-(U$17-CANL)") (class "Default")
      (node (ref "R3") (pin "1") (pinfunction "1_1") (pintype "passive"))
      (node (ref "U$17") (pin "6") (pinfunction "CANL_6") (pintype "bidirectional"))
      (node (ref "U$27") (pin "P$4") (pinfunction "4_P$4") (pintype "passive"))
      (node (ref "U$9") (pin "P$4") (pinfunction "4_P$4") (pintype "passive"))
    )
    (net (code "124") (name "Net-(U$58-BLUE)") (class "Default")
      (node (ref "R47") (pin "2") (pinfunction "2_2") (pintype "passive"))
      (node (ref "U$58") (pin "4") (pinfunction "BLUE_4") (pintype "bidirectional"))
    )
    (net (code "125") (name "Net-(U$58-GREEN)") (class "Default")
      (node (ref "R46") (pin "2") (pinfunction "2_2") (pintype "passive"))
      (node (ref "U$58") (pin "2") (pinfunction "GREEN_2") (pintype "bidirectional"))
    )
    (net (code "126") (name "Net-(U$58-RED)") (class "Default")
      (node (ref "R45") (pin "2") (pinfunction "2_2") (pintype "passive"))
      (node (ref "U$58") (pin "1") (pinfunction "RED_1") (pintype "bidirectional"))
    )
    (net (code "127") (name "Net-(U$68A-I)") (class "Default")
      (node (ref "U$68") (pin "2") (pinfunction "I_2") (pintype "input"))
      (node (ref "U$82") (pin "2") (pinfunction "2_2") (pintype "bidirectional"))
      (node (ref "U$82") (pin "5") (pinfunction "5_5") (pintype "bidirectional"))
    )
    (net (code "128") (name "Net-(U$75-VBUS)") (class "Default")
      (node (ref "U$75") (pin "1") (pinfunction "VBUS_1") (pintype "bidirectional"))
      (node (ref "U$76") (pin "1") (pinfunction "1_1") (pintype "passive"))
    )
    (net (code "129") (name "Net-(X2B-S)") (class "Default")
      (node (ref "U$40") (pin "1") (pinfunction "1_1") (pintype "passive"))
      (node (ref "X2") (pin "10") (pinfunction "S_10") (pintype "passive"))
    )
    (net (code "130") (name "Net-(X2C-S)") (class "Default")
      (node (ref "U$41") (pin "1") (pinfunction "1_1") (pintype "passive"))
      (node (ref "X2") (pin "11") (pinfunction "S_11") (pintype "passive"))
    )
    (net (code "131") (name "Net-(X2D-S)") (class "Default")
      (node (ref "U$42") (pin "1") (pinfunction "1_1") (pintype "passive"))
      (node (ref "X2") (pin "12") (pinfunction "S_12") (pintype "passive"))
    )
    (net (code "132") (name "Net-(X2E-S)") (class "Default")
      (node (ref "U$43") (pin "1") (pinfunction "1_1") (pintype "passive"))
      (node (ref "X2") (pin "13") (pinfunction "S_13") (pintype "passive"))
    )
    (net (code "133") (name "Net-(X2F-S)") (class "Default")
      (node (ref "U$44") (pin "1") (pinfunction "1_1") (pintype "passive"))
      (node (ref "X2") (pin "14") (pinfunction "S_14") (pintype "passive"))
    )
    (net (code "134") (name "Net-(X2G-S)") (class "Default")
      (node (ref "U$45") (pin "1") (pinfunction "1_1") (pintype "passive"))
      (node (ref "X2") (pin "15") (pinfunction "S_15") (pintype "passive"))
    )
    (net (code "135") (name "Net-(X2H-S)") (class "Default")
      (node (ref "U$46") (pin "1") (pinfunction "1_1") (pintype "passive"))
      (node (ref "X2") (pin "16") (pinfunction "S_16") (pintype "passive"))
    )
    (net (code "136") (name "Net-(X2J-S)") (class "Default")
      (node (ref "U$33") (pin "1") (pinfunction "1_1") (pintype "passive"))
      (node (ref "X2") (pin "3") (pinfunction "S_3") (pintype "passive"))
    )
    (net (code "137") (name "Net-(X2K-S)") (class "Default")
      (node (ref "U$34") (pin "1") (pinfunction "1_1") (pintype "passive"))
      (node (ref "X2") (pin "4") (pinfunction "S_4") (pintype "passive"))
    )
    (net (code "138") (name "Net-(X2L-S)") (class "Default")
      (node (ref "U$35") (pin "1") (pinfunction "1_1") (pintype "passive"))
      (node (ref "X2") (pin "5") (pinfunction "S_5") (pintype "passive"))
    )
    (net (code "139") (name "Net-(X2M-S)") (class "Default")
      (node (ref "U$36") (pin "1") (pinfunction "1_1") (pintype "passive"))
      (node (ref "X2") (pin "6") (pinfunction "S_6") (pintype "passive"))
    )
    (net (code "140") (name "Net-(X2N-S)") (class "Default")
      (node (ref "U$37") (pin "1") (pinfunction "1_1") (pintype "passive"))
      (node (ref "X2") (pin "7") (pinfunction "S_7") (pintype "passive"))
    )
    (net (code "141") (name "Net-(X2O-S)") (class "Default")
      (node (ref "U$38") (pin "1") (pinfunction "1_1") (pintype "passive"))
      (node (ref "X2") (pin "8") (pinfunction "S_8") (pintype "passive"))
    )
    (net (code "142") (name "Net-(X2P-S)") (class "Default")
      (node (ref "U$39") (pin "1") (pinfunction "1_1") (pintype "passive"))
      (node (ref "X2") (pin "9") (pinfunction "S_9") (pintype "passive"))
    )
    (net (code "143") (name "VCC") (class "Default")
      (node (ref "C10") (pin "2") (pinfunction "2_2") (pintype "passive"))
      (node (ref "C11") (pin "2") (pinfunction "2_2") (pintype "passive"))
      (node (ref "C3") (pin "1") (pinfunction "1_1") (pintype "passive"))
      (node (ref "C34") (pin "2") (pinfunction "2_2") (pintype "passive"))
      (node (ref "C6") (pin "2") (pinfunction "2_2") (pintype "passive"))
      (node (ref "C7") (pin "2") (pinfunction "2_2") (pintype "passive"))
      (node (ref "D1") (pin "A") (pinfunction "A_A") (pintype "passive"))
      (node (ref "IC4") (pin "20") (pinfunction "VCC_20") (pintype "power_in"))
      (node (ref "IC6") (pin "42") (pinfunction "RB6_42") (pintype "bidirectional"))
      (node (ref "R41") (pin "1") (pinfunction "1_1") (pintype "passive"))
      (node (ref "SG2") (pin "1") (pinfunction "1_1") (pintype "passive"))
      (node (ref "U$11") (pin "SENSE") (pinfunction "SENSE_SENSE") (pintype "bidirectional"))
      (node (ref "U$11") (pin "VOUT") (pinfunction "VOUT_VOUT") (pintype "bidirectional"))
      (node (ref "U$17") (pin "3") (pinfunction "VDD_3") (pintype "power_in"))
      (node (ref "U$26") (pin "1") (pinfunction "IN_1") (pintype "power_in"))
      (node (ref "U$27") (pin "P$1") (pinfunction "1_P$1") (pintype "passive"))
      (node (ref "U$27") (pin "P$2") (pinfunction "2_P$2") (pintype "passive"))
      (node (ref "U$27") (pin "P$3") (pinfunction "3_P$3") (pintype "passive"))
      (node (ref "U$29") (pin "1") (pinfunction "VBUS_1") (pintype "bidirectional"))
      (node (ref "U$3") (pin "3") (pinfunction "VDD_3") (pintype "power_in"))
      (node (ref "U$4") (pin "P$1") (pinfunction "1_P$1") (pintype "passive"))
      (node (ref "U$4") (pin "P$2") (pinfunction "2_P$2") (pintype "passive"))
      (node (ref "U$4") (pin "P$3") (pinfunction "3_P$3") (pintype "passive"))
      (node (ref "U$5") (pin "P$1") (pinfunction "1_P$1") (pintype "passive"))
      (node (ref "U$5") (pin "P$2") (pinfunction "2_P$2") (pintype "passive"))
      (node (ref "U$5") (pin "P$3") (pinfunction "3_P$3") (pintype "passive"))
      (node (ref "U$76") (pin "2") (pinfunction "2_2") (pintype "passive"))
      (node (ref "U$9") (pin "P$1") (pinfunction "1_P$1") (pintype "passive"))
      (node (ref "U$9") (pin "P$2") (pinfunction "2_P$2") (pintype "passive"))
      (node (ref "U$9") (pin "P$3") (pinfunction "3_P$3") (pintype "passive"))
      (node (ref "X4") (pin "1") (pinfunction "1_1") (pintype "bidirectional"))
      (node (ref "X5") (pin "1") (pinfunction "1_1") (pintype "bidirectional"))
    )
    (net (code "144") (name "unconnected-(IC4-CBUS0-Pad23)") (class "Default")
      (node (ref "IC4") (pin "23") (pinfunction "CBUS0_23") (pintype "bidirectional"))
    )
    (net (code "145") (name "unconnected-(IC4-CBUS1-Pad22)") (class "Default")
      (node (ref "IC4") (pin "22") (pinfunction "CBUS1_22") (pintype "bidirectional"))
    )
    (net (code "146") (name "unconnected-(IC4-CBUS2-Pad13)") (class "Default")
      (node (ref "IC4") (pin "13") (pinfunction "CBUS2_13") (pintype "bidirectional"))
    )
    (net (code "147") (name "unconnected-(IC4-CBUS3-Pad14)") (class "Default")
      (node (ref "IC4") (pin "14") (pinfunction "CBUS3_14") (pintype "bidirectional"))
    )
    (net (code "148") (name "unconnected-(IC4-CBUS4-Pad12)") (class "Default")
      (node (ref "IC4") (pin "12") (pinfunction "CBUS4_12") (pintype "bidirectional"))
    )
    (net (code "149") (name "unconnected-(IC4-OSCI-Pad27)") (class "Default")
      (node (ref "IC4") (pin "27") (pinfunction "OSCI_27") (pintype "input"))
    )
    (net (code "150") (name "unconnected-(IC4-OSCO-Pad28)") (class "Default")
      (node (ref "IC4") (pin "28") (pinfunction "OSCO_28") (pintype "output"))
    )
    (net (code "151") (name "unconnected-(IC4-~{CTS}-Pad11)") (class "Default")
      (node (ref "IC4") (pin "11") (pinfunction "~{CTS}_11") (pintype "input"))
    )
    (net (code "152") (name "unconnected-(IC4-~{DCD}-Pad10)") (class "Default")
      (node (ref "IC4") (pin "10") (pinfunction "~{DCD}_10") (pintype "input"))
    )
    (net (code "153") (name "unconnected-(IC4-~{DSR}-Pad9)") (class "Default")
      (node (ref "IC4") (pin "9") (pinfunction "~{DSR}_9") (pintype "input"))
    )
    (net (code "154") (name "unconnected-(IC4-~{DTR}-Pad2)") (class "Default")
      (node (ref "IC4") (pin "2") (pinfunction "~{DTR}_2") (pintype "output"))
    )
    (net (code "155") (name "unconnected-(IC4-~{RESET}-Pad19)") (class "Default")
      (node (ref "IC4") (pin "19") (pinfunction "~{RESET}_19") (pintype "input"))
    )
    (net (code "156") (name "unconnected-(IC4-~{RI}-Pad6)") (class "Default")
      (node (ref "IC4") (pin "6") (pinfunction "~{RI}_6") (pintype "input"))
    )
    (net (code "157") (name "unconnected-(IC4-~{RTS}-Pad3)") (class "Default")
      (node (ref "IC4") (pin "3") (pinfunction "~{RTS}_3") (pintype "output"))
    )
    (net (code "158") (name "unconnected-(IC6-RA0-Pad19)") (class "Default")
      (node (ref "IC6") (pin "19") (pinfunction "RA0_19") (pintype "bidirectional"))
    )
    (net (code "159") (name "unconnected-(IC6-RA1-Pad20)") (class "Default")
      (node (ref "IC6") (pin "20") (pinfunction "RA1_20") (pintype "bidirectional"))
    )
    (net (code "160") (name "unconnected-(IC6-RA2-Pad30)") (class "Default")
      (node (ref "IC6") (pin "30") (pinfunction "RA2_30") (pintype "bidirectional"))
    )
    (net (code "161") (name "unconnected-(IC6-RA3-Pad31)") (class "Default")
      (node (ref "IC6") (pin "31") (pinfunction "RA3_31") (pintype "bidirectional"))
    )
    (net (code "162") (name "unconnected-(IC6-RA4-Pad34)") (class "Default")
      (node (ref "IC6") (pin "34") (pinfunction "RA4_34") (pintype "bidirectional"))
    )
    (net (code "163") (name "unconnected-(IC6-RB2-Pad23)") (class "Default")
      (node (ref "IC6") (pin "23") (pinfunction "RB2_23") (pintype "bidirectional"))
    )
    (net (code "164") (name "unconnected-(IC6-RB3-Pad24)") (class "Default")
      (node (ref "IC6") (pin "24") (pinfunction "RB3_24") (pintype "bidirectional"))
    )
    (net (code "165") (name "unconnected-(IC6-RB4-Pad33)") (class "Default")
      (node (ref "IC6") (pin "33") (pinfunction "RB4_33") (pintype "bidirectional"))
    )
    (net (code "166") (name "unconnected-(IC6-RB5-Pad41)") (class "Default")
      (node (ref "IC6") (pin "41") (pinfunction "RB5_41") (pintype "bidirectional"))
    )
    (net (code "167") (name "unconnected-(IC6-RB7-Pad43)") (class "Default")
      (node (ref "IC6") (pin "43") (pinfunction "RB7_43") (pintype "bidirectional"))
    )
    (net (code "168") (name "unconnected-(IC6-RB8-Pad44)") (class "Default")
      (node (ref "IC6") (pin "44") (pinfunction "RB8_44") (pintype "bidirectional"))
    )
    (net (code "169") (name "unconnected-(IC6-RB13-Pad11)") (class "Default")
      (node (ref "IC6") (pin "11") (pinfunction "RB13_11") (pintype "bidirectional"))
    )
    (net (code "170") (name "unconnected-(IC6-RC0-Pad25)") (class "Default")
      (node (ref "IC6") (pin "25") (pinfunction "RC0_25") (pintype "bidirectional"))
    )
    (net (code "171") (name "unconnected-(IC6-RC1-Pad26)") (class "Default")
      (node (ref "IC6") (pin "26") (pinfunction "RC1_26") (pintype "bidirectional"))
    )
    (net (code "172") (name "unconnected-(IC6-RC2-Pad27)") (class "Default")
      (node (ref "IC6") (pin "27") (pinfunction "RC2_27") (pintype "bidirectional"))
    )
    (net (code "173") (name "unconnected-(IC6-RC3-Pad36)") (class "Default")
      (node (ref "IC6") (pin "36") (pinfunction "RC3_36") (pintype "bidirectional"))
    )
    (net (code "174") (name "unconnected-(IC6-RC4-Pad37)") (class "Default")
      (node (ref "IC6") (pin "37") (pinfunction "RC4_37") (pintype "bidirectional"))
    )
    (net (code "175") (name "unconnected-(IC6-RC5-Pad38)") (class "Default")
      (node (ref "IC6") (pin "38") (pinfunction "RC5_38") (pintype "bidirectional"))
    )
    (net (code "176") (name "unconnected-(IC6-TCK-Pad13)") (class "Default")
      (node (ref "IC6") (pin "13") (pinfunction "TCK_13") (pintype "input"))
    )
    (net (code "177") (name "unconnected-(IC6-TDI-Pad35)") (class "Default")
      (node (ref "IC6") (pin "35") (pinfunction "TDI_35") (pintype "input"))
    )
    (net (code "178") (name "unconnected-(IC6-TDO-Pad32)") (class "Default")
      (node (ref "IC6") (pin "32") (pinfunction "TDO_32") (pintype "output"))
    )
    (net (code "179") (name "unconnected-(IC6-TMS-Pad12)") (class "Default")
      (node (ref "IC6") (pin "12") (pinfunction "TMS_12") (pintype "input"))
    )
    (net (code "180") (name "unconnected-(S6-S-Pad3)") (class "Default")
      (node (ref "S6") (pin "3") (pinfunction "S_3") (pintype "passive"))
    )
    (net (code "181") (name "unconnected-(U$1-P05{slash}DA1-Pad100)") (class "Default")
      (node (ref "U$1") (pin "100") (pinfunction "P05/DA1_100") (pintype "bidirectional"))
    )
    (net (code "182") (name "unconnected-(U$1-P07-Pad98)") (class "Default")
      (node (ref "U$1") (pin "98") (pinfunction "P07_98") (pintype "bidirectional"))
    )
    (net (code "183") (name "unconnected-(U$1-P17{slash}MTIOC3A{slash}MTIOC3B{slash}SCK1{slash}TXD3-Pad29)") (class "Default")
      (node (ref "U$1") (pin "29") (pinfunction "P17/MTIOC3A/MTIOC3B/SCK1/TXD3_29") (pintype "bidirectional"))
    )
    (net (code "184") (name "unconnected-(U$1-P51{slash}SCK2-Pad43)") (class "Default")
      (node (ref "U$1") (pin "43") (pinfunction "P51/SCK2_43") (pintype "bidirectional"))
    )
    (net (code "185") (name "unconnected-(U$1-P53{slash}BCLK-Pad41)") (class "Default")
      (node (ref "U$1") (pin "41") (pinfunction "P53/BCLK_41") (pintype "bidirectional"))
    )
    (net (code "186") (name "unconnected-(U$1-PB0{slash}RXD6-Pad61)") (class "Default")
      (node (ref "U$1") (pin "61") (pinfunction "PB0/RXD6_61") (pintype "bidirectional"))
    )
    (net (code "187") (name "unconnected-(U$1-PB1{slash}MTIOC0C{slash}MTIOC4C{slash}TXD6-Pad59)") (class "Default")
      (node (ref "U$1") (pin "59") (pinfunction "PB1/MTIOC0C/MTIOC4C/TXD6_59") (pintype "bidirectional"))
    )
    (net (code "188") (name "unconnected-(U$1-PB2-Pad58)") (class "Default")
      (node (ref "U$1") (pin "58") (pinfunction "PB2_58") (pintype "bidirectional"))
    )
    (net (code "189") (name "unconnected-(U$1-PB6{slash}MTIOC3D{slash}RXD9-Pad54)") (class "Default")
      (node (ref "U$1") (pin "54") (pinfunction "PB6/MTIOC3D/RXD9_54") (pintype "bidirectional"))
    )
    (net (code "190") (name "unconnected-(U$1-PC2{slash}MTIOC4B{slash}TCLKA{slash}RXD5-Pad50)") (class "Default")
      (node (ref "U$1") (pin "50") (pinfunction "PC2/MTIOC4B/TCLKA/RXD5_50") (pintype "bidirectional"))
    )
    (net (code "191") (name "unconnected-(U$1-PC3{slash}MTIOC4D{slash}TCLKB{slash}TXD5-Pad49)") (class "Default")
      (node (ref "U$1") (pin "49") (pinfunction "PC3/MTIOC4D/TCLKB/TXD5_49") (pintype "bidirectional"))
    )
    (net (code "192") (name "unconnected-(U$1-PC6{slash}MTIOC3C{slash}MTCLKA{slash}RXD8-Pad46)") (class "Default")
      (node (ref "U$1") (pin "46") (pinfunction "PC6/MTIOC3C/MTCLKA/RXD8_46") (pintype "bidirectional"))
    )
    (net (code "193") (name "unconnected-(U$1-PE3{slash}MTIOC4B{slash}AN1-Pad75)") (class "Default")
      (node (ref "U$1") (pin "75") (pinfunction "PE3/MTIOC4B/AN1_75") (pintype "bidirectional"))
    )
    (net (code "194") (name "unconnected-(U$1-PE4{slash}MTIOC4D{slash}MTIOC1A{slash}AN2-Pad74)") (class "Default")
      (node (ref "U$1") (pin "74") (pinfunction "PE4/MTIOC4D/MTIOC1A/AN2_74") (pintype "bidirectional"))
    )
    (net (code "195") (name "unconnected-(U$1-PE5{slash}MTIOC4C{slash}MTIOC2B{slash}AN3-Pad73)") (class "Default")
      (node (ref "U$1") (pin "73") (pinfunction "PE5/MTIOC4C/MTIOC2B/AN3_73") (pintype "bidirectional"))
    )
    (net (code "196") (name "unconnected-(U$1-PE6{slash}AN4-Pad72)") (class "Default")
      (node (ref "U$1") (pin "72") (pinfunction "PE6/AN4_72") (pintype "bidirectional"))
    )
    (net (code "197") (name "unconnected-(U$1-PE7{slash}AN5-Pad71)") (class "Default")
      (node (ref "U$1") (pin "71") (pinfunction "PE7/AN5_71") (pintype "bidirectional"))
    )
    (net (code "198") (name "unconnected-(U$1-PJ3{slash}MITIOC3C-Pad4)") (class "Default")
      (node (ref "U$1") (pin "4") (pinfunction "PJ3/MITIOC3C_4") (pintype "bidirectional"))
    )
    (net (code "199") (name "unconnected-(U$1-XCOUT-Pad9)") (class "Default")
      (node (ref "U$1") (pin "9") (pinfunction "XCOUT_9") (pintype "bidirectional"))
    )
    (net (code "200") (name "unconnected-(U$2-ID(NC)-Pad4)") (class "Default")
      (node (ref "U$2") (pin "4") (pinfunction "ID(NC)_4") (pintype "bidirectional"))
    )
    (net (code "201") (name "unconnected-(U$11-PadPGOOD)") (class "Default")
      (node (ref "U$11") (pin "PGOOD") (pinfunction "PGOOD_PGOOD") (pintype "bidirectional"))
    )
    (net (code "202") (name "unconnected-(U$32-ES_CL-Pad6)") (class "Default")
      (node (ref "U$32") (pin "6") (pinfunction "ES_CL_6") (pintype "bidirectional"))
    )
    (net (code "203") (name "unconnected-(U$32-ES_DA-Pad5)") (class "Default")
      (node (ref "U$32") (pin "5") (pinfunction "ES_DA_5") (pintype "bidirectional"))
    )
    (net (code "204") (name "unconnected-(U$32-FSYNC-Pad7)") (class "Default")
      (node (ref "U$32") (pin "7") (pinfunction "FSYNC_7") (pintype "bidirectional"))
    )
    (net (code "205") (name "unconnected-(X1K-S-Pad6)") (class "Default")
      (node (ref "X1") (pin "6") (pinfunction "S_6") (pintype "passive"))
    )
  )
)
